# DM04mux.net
KiCad netlist of a schematic drawn in EAGLE
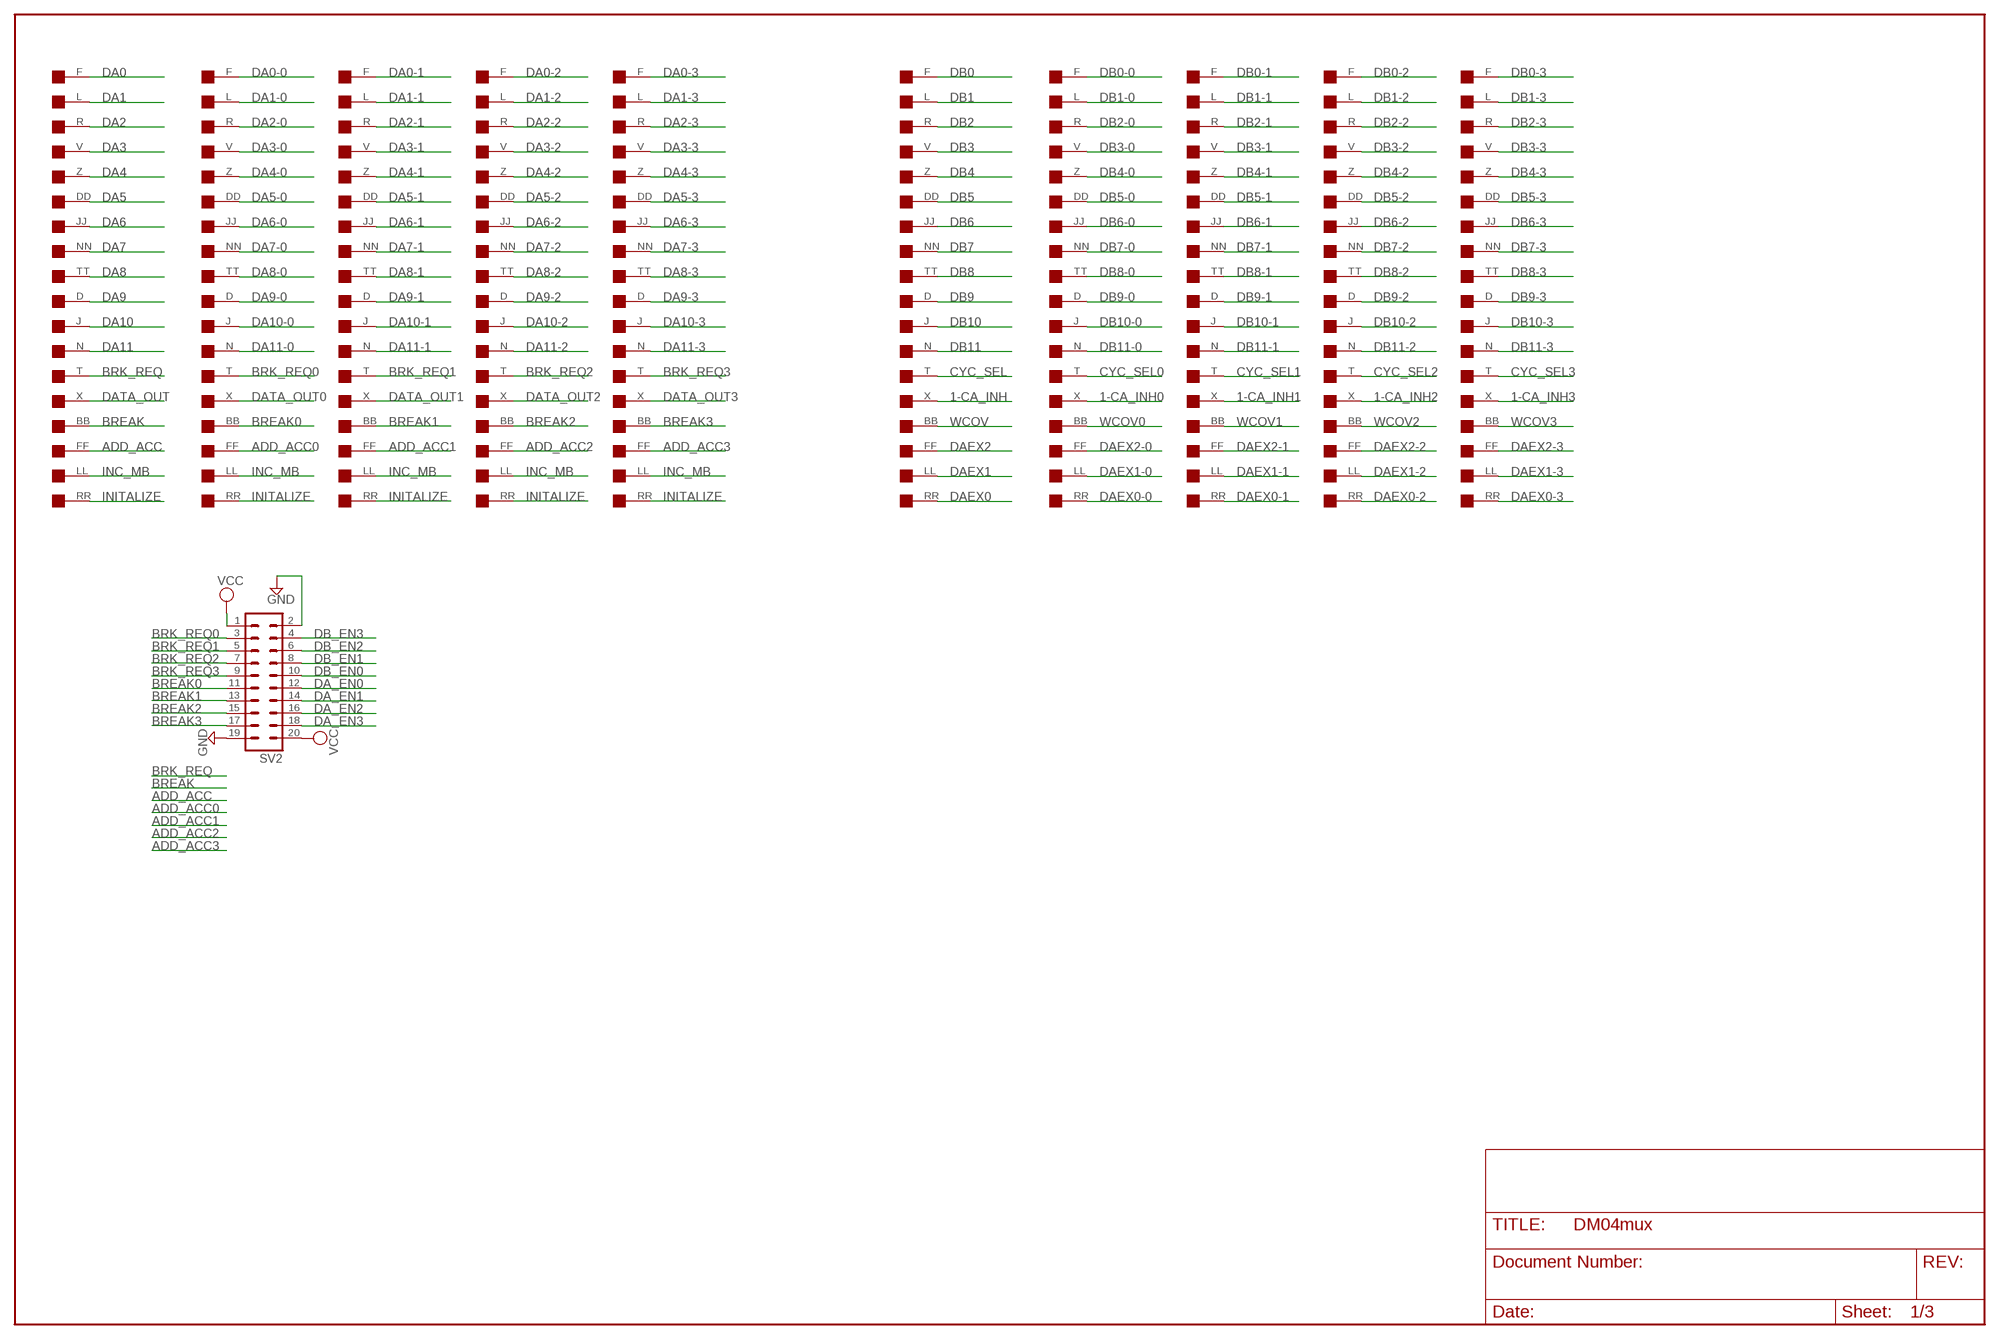
[diagram p0: schematic, sheet 1]
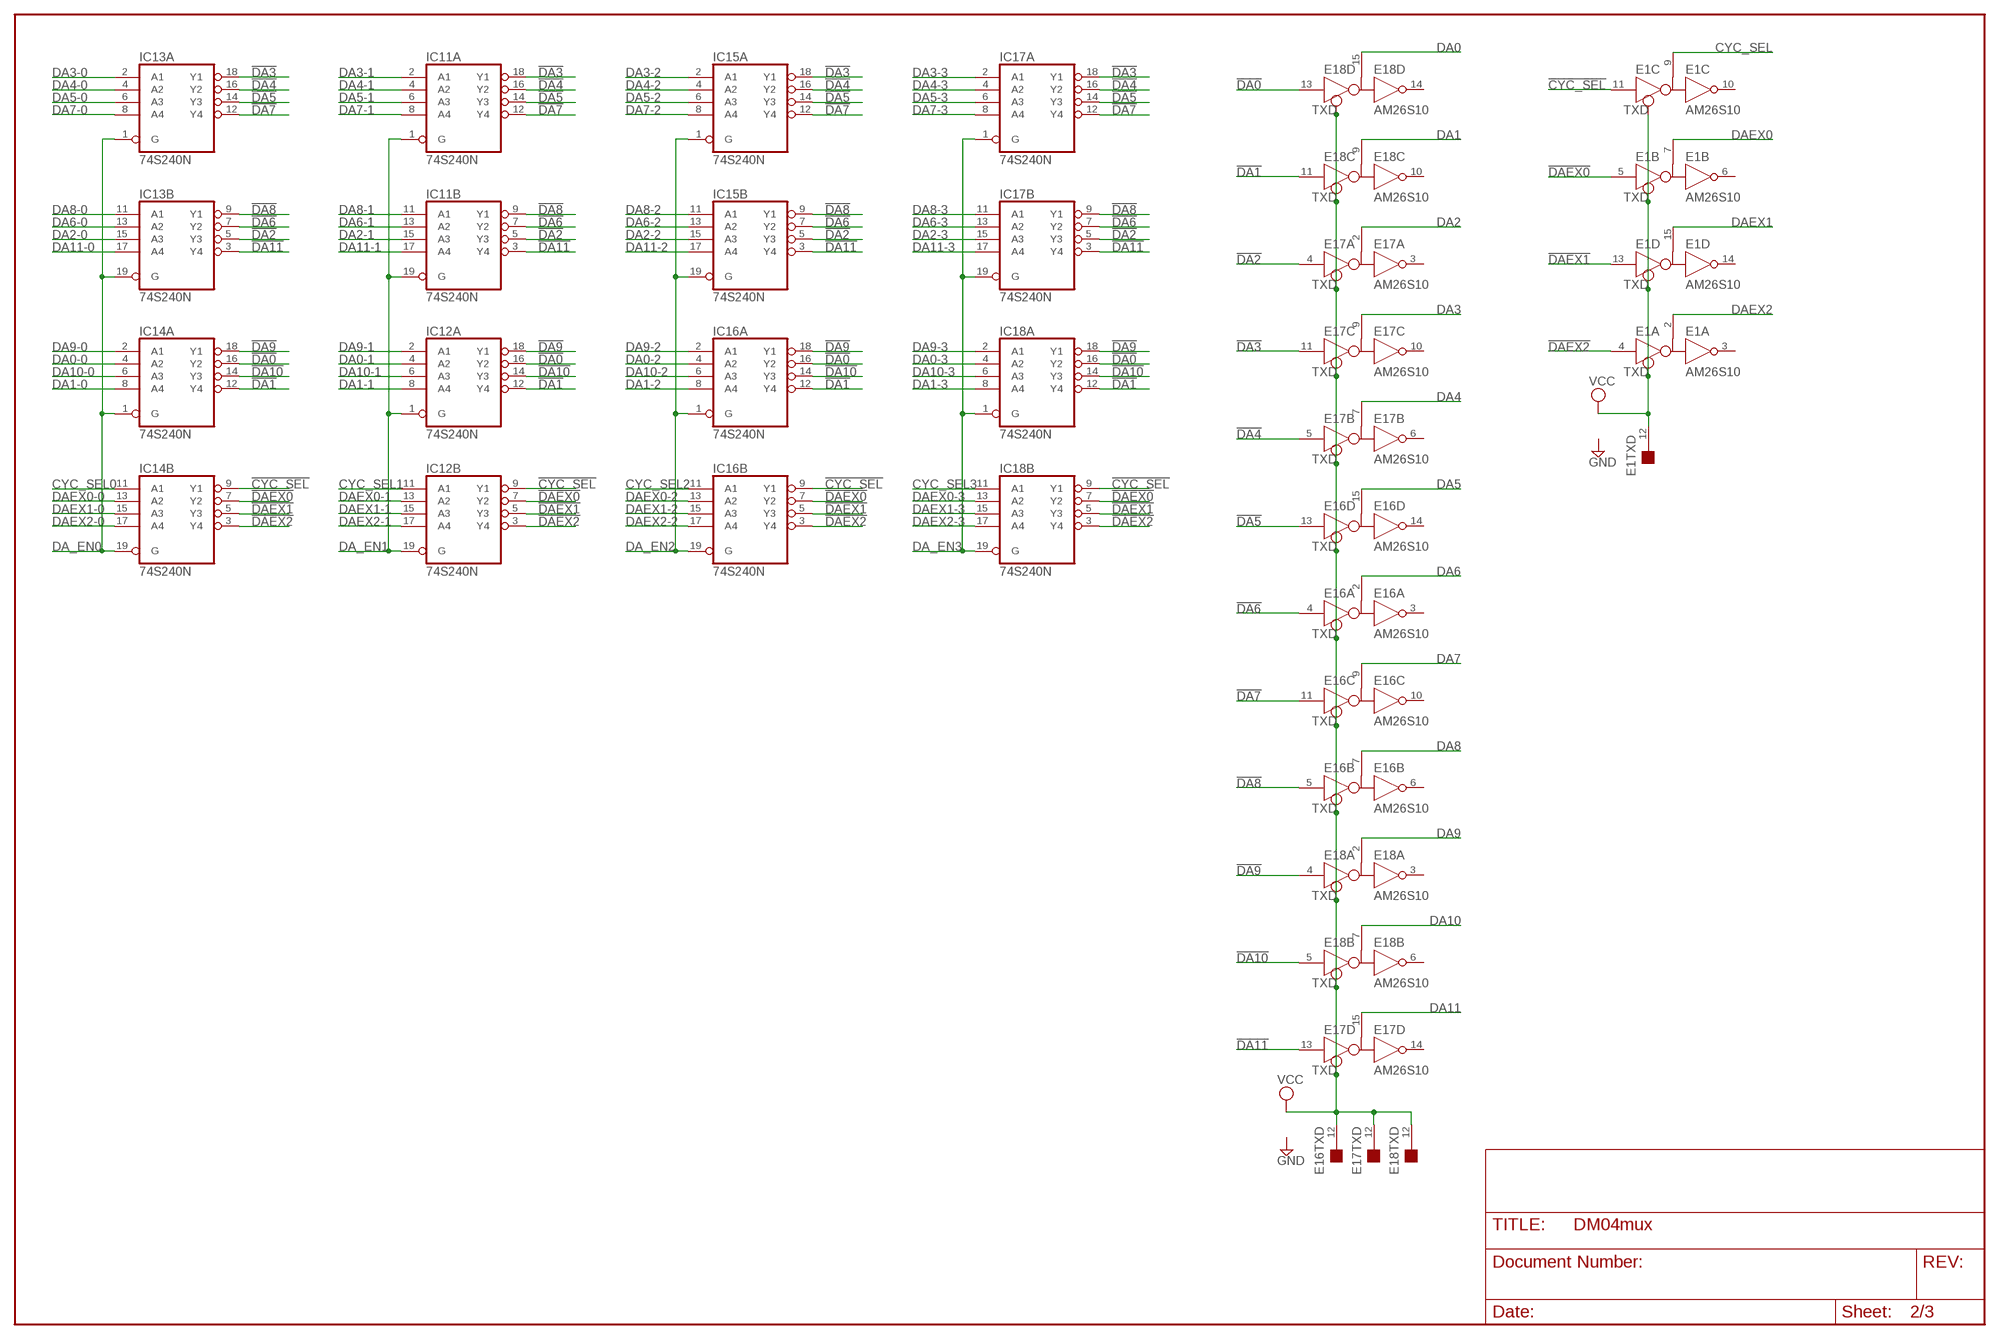
[diagram p1: schematic, sheet 2]
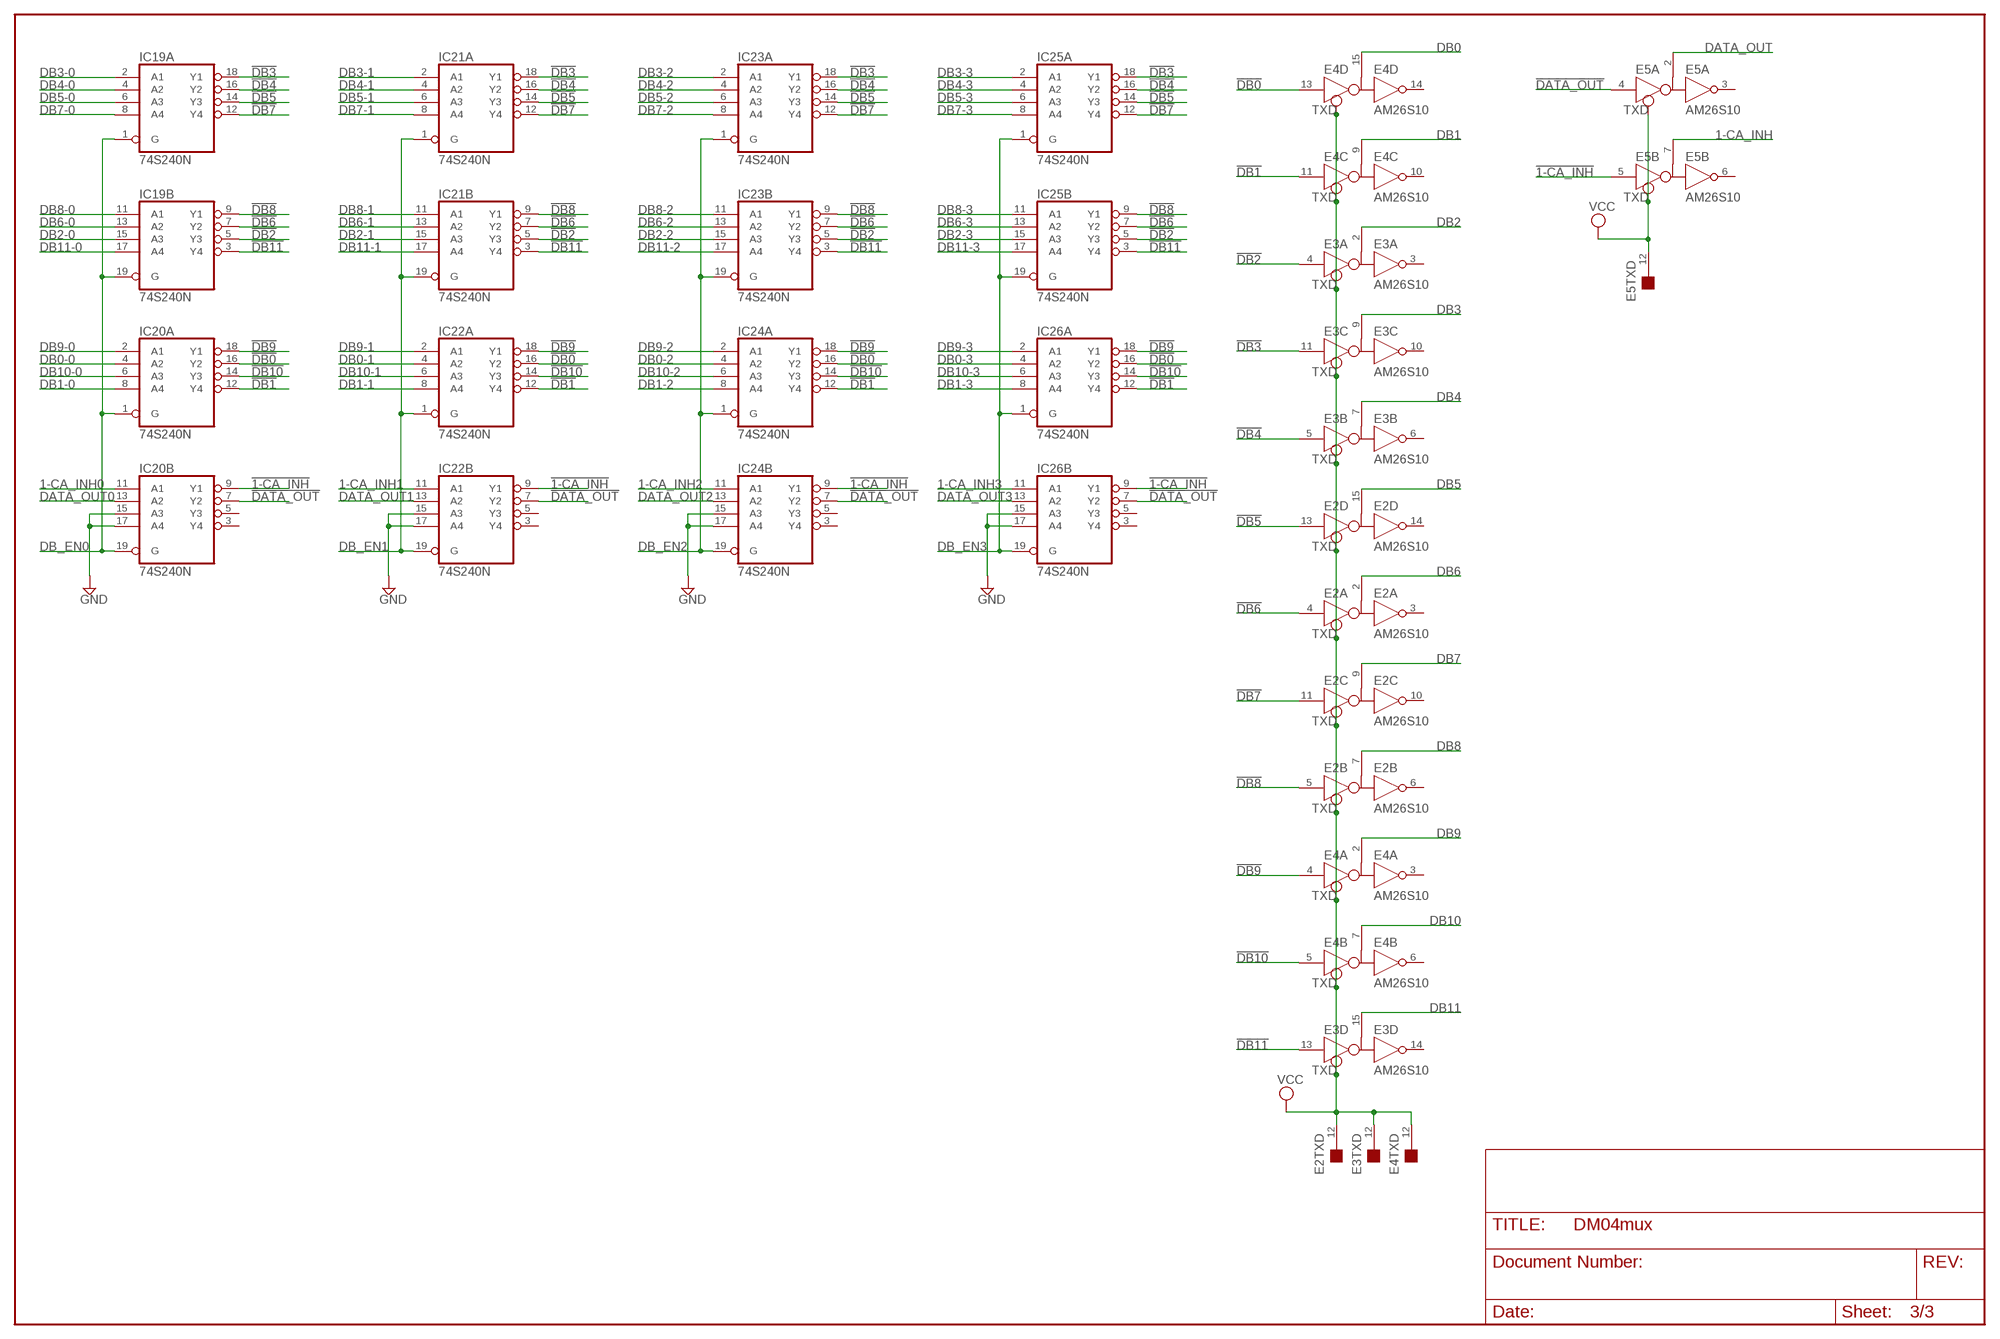
[diagram p2: schematic, sheet 3]

(export (version "E")
  (design (tool "Eeschema 10.0.6"))
  (components
    (comp (ref "SV2")
      (value "MA10-2")
      (footprint "eagle-import:MA10-2")
      (libsource (lib "eagle-import") (part "MA10-2"))
    )
    (comp (ref "U$1")
      (value "BC08J")
      (footprint "eagle-import:DEC40PINV")
      (libsource (lib "eagle-import") (part "BC08J"))
    )
    (comp (ref "U$2")
      (value "BC08J")
      (footprint "eagle-import:DEC40PINV")
      (libsource (lib "eagle-import") (part "BC08J"))
    )
    (comp (ref "U$3")
      (value "BC08J")
      (footprint "eagle-import:DEC40PINV")
      (libsource (lib "eagle-import") (part "BC08J"))
    )
    (comp (ref "U$4")
      (value "BC08J")
      (footprint "eagle-import:DEC40PINV")
      (libsource (lib "eagle-import") (part "BC08J"))
    )
    (comp (ref "U$5")
      (value "BC08J")
      (footprint "eagle-import:DEC40PINV")
      (libsource (lib "eagle-import") (part "BC08J"))
    )
    (comp (ref "U$6")
      (value "BC08J")
      (footprint "eagle-import:DEC40PINV")
      (libsource (lib "eagle-import") (part "BC08J"))
    )
    (comp (ref "U$7")
      (value "BC08J")
      (footprint "eagle-import:DEC40PINV")
      (libsource (lib "eagle-import") (part "BC08J"))
    )
    (comp (ref "U$8")
      (value "BC08J")
      (footprint "eagle-import:DEC40PINV")
      (libsource (lib "eagle-import") (part "BC08J"))
    )
    (comp (ref "U$9")
      (value "BC08J")
      (footprint "eagle-import:DEC40PINV")
      (libsource (lib "eagle-import") (part "BC08J"))
    )
    (comp (ref "U$10")
      (value "BC08J")
      (footprint "eagle-import:DEC40PINV")
      (libsource (lib "eagle-import") (part "BC08J"))
    )
    (comp (ref "E1")
      (value "AM26S10")
      (footprint "eagle-import:DIL16")
      (libsource (lib "eagle-import") (part "AM26S10"))
    )
    (comp (ref "E16")
      (value "AM26S10")
      (footprint "eagle-import:DIL16")
      (libsource (lib "eagle-import") (part "AM26S10"))
    )
    (comp (ref "E17")
      (value "AM26S10")
      (footprint "eagle-import:DIL16")
      (libsource (lib "eagle-import") (part "AM26S10"))
    )
    (comp (ref "E18")
      (value "AM26S10")
      (footprint "eagle-import:DIL16")
      (libsource (lib "eagle-import") (part "AM26S10"))
    )
    (comp (ref "IC11")
      (value "74S240N")
      (footprint "eagle-import:DIL20")
      (libsource (lib "eagle-import") (part "74240NS"))
    )
    (comp (ref "IC12")
      (value "74S240N")
      (footprint "eagle-import:DIL20")
      (libsource (lib "eagle-import") (part "74240NS"))
    )
    (comp (ref "IC13")
      (value "74S240N")
      (footprint "eagle-import:DIL20")
      (libsource (lib "eagle-import") (part "74240NS"))
    )
    (comp (ref "IC14")
      (value "74S240N")
      (footprint "eagle-import:DIL20")
      (libsource (lib "eagle-import") (part "74240NS"))
    )
    (comp (ref "IC15")
      (value "74S240N")
      (footprint "eagle-import:DIL20")
      (libsource (lib "eagle-import") (part "74240NS"))
    )
    (comp (ref "IC16")
      (value "74S240N")
      (footprint "eagle-import:DIL20")
      (libsource (lib "eagle-import") (part "74240NS"))
    )
    (comp (ref "IC17")
      (value "74S240N")
      (footprint "eagle-import:DIL20")
      (libsource (lib "eagle-import") (part "74240NS"))
    )
    (comp (ref "IC18")
      (value "74S240N")
      (footprint "eagle-import:DIL20")
      (libsource (lib "eagle-import") (part "74240NS"))
    )
    (comp (ref "E2")
      (value "AM26S10")
      (footprint "eagle-import:DIL16")
      (libsource (lib "eagle-import") (part "AM26S10"))
    )
    (comp (ref "E3")
      (value "AM26S10")
      (footprint "eagle-import:DIL16")
      (libsource (lib "eagle-import") (part "AM26S10"))
    )
    (comp (ref "E4")
      (value "AM26S10")
      (footprint "eagle-import:DIL16")
      (libsource (lib "eagle-import") (part "AM26S10"))
    )
    (comp (ref "E5")
      (value "AM26S10")
      (footprint "eagle-import:DIL16")
      (libsource (lib "eagle-import") (part "AM26S10"))
    )
    (comp (ref "IC19")
      (value "74S240N")
      (footprint "eagle-import:DIL20")
      (libsource (lib "eagle-import") (part "74240NS"))
    )
    (comp (ref "IC20")
      (value "74S240N")
      (footprint "eagle-import:DIL20")
      (libsource (lib "eagle-import") (part "74240NS"))
    )
    (comp (ref "IC21")
      (value "74S240N")
      (footprint "eagle-import:DIL20")
      (libsource (lib "eagle-import") (part "74240NS"))
    )
    (comp (ref "IC22")
      (value "74S240N")
      (footprint "eagle-import:DIL20")
      (libsource (lib "eagle-import") (part "74240NS"))
    )
    (comp (ref "IC23")
      (value "74S240N")
      (footprint "eagle-import:DIL20")
      (libsource (lib "eagle-import") (part "74240NS"))
    )
    (comp (ref "IC24")
      (value "74S240N")
      (footprint "eagle-import:DIL20")
      (libsource (lib "eagle-import") (part "74240NS"))
    )
    (comp (ref "IC25")
      (value "74S240N")
      (footprint "eagle-import:DIL20")
      (libsource (lib "eagle-import") (part "74240NS"))
    )
    (comp (ref "IC26")
      (value "74S240N")
      (footprint "eagle-import:DIL20")
      (libsource (lib "eagle-import") (part "74240NS"))
    )
  )
  (nets
    (net (code "1") (name "1-CA_INH") (class "Default")
      (node (ref "E5") (pin "7") (pinfunction "B_7") (pintype "bidirectional"))
      (node (ref "U$6") (pin "X") (pinfunction "1_X") (pintype "bidirectional"))
    )
    (net (code "2") (name "1-CA_INH0") (class "Default")
      (node (ref "IC20") (pin "11") (pinfunction "A1_11") (pintype "input"))
      (node (ref "U$7") (pin "X") (pinfunction "1_X") (pintype "bidirectional"))
    )
    (net (code "3") (name "1-CA_INH1") (class "Default")
      (node (ref "IC22") (pin "11") (pinfunction "A1_11") (pintype "input"))
      (node (ref "U$8") (pin "X") (pinfunction "1_X") (pintype "bidirectional"))
    )
    (net (code "4") (name "1-CA_INH2") (class "Default")
      (node (ref "IC24") (pin "11") (pinfunction "A1_11") (pintype "input"))
      (node (ref "U$9") (pin "X") (pinfunction "1_X") (pintype "bidirectional"))
    )
    (net (code "5") (name "1-CA_INH3") (class "Default")
      (node (ref "IC26") (pin "11") (pinfunction "A1_11") (pintype "input"))
      (node (ref "U$10") (pin "X") (pinfunction "1_X") (pintype "bidirectional"))
    )
    (net (code "6") (name "ADD_ACC") (class "Default")
      (node (ref "U$1") (pin "FF") (pinfunction "1_FF") (pintype "bidirectional"))
    )
    (net (code "7") (name "ADD_ACC0") (class "Default")
      (node (ref "U$2") (pin "FF") (pinfunction "1_FF") (pintype "bidirectional"))
    )
    (net (code "8") (name "ADD_ACC1") (class "Default")
      (node (ref "U$3") (pin "FF") (pinfunction "1_FF") (pintype "bidirectional"))
    )
    (net (code "9") (name "ADD_ACC2") (class "Default")
      (node (ref "U$4") (pin "FF") (pinfunction "1_FF") (pintype "bidirectional"))
    )
    (net (code "10") (name "ADD_ACC3") (class "Default")
      (node (ref "U$5") (pin "FF") (pinfunction "1_FF") (pintype "bidirectional"))
    )
    (net (code "11") (name "BREAK") (class "Default")
      (node (ref "U$1") (pin "BB") (pinfunction "1_BB") (pintype "bidirectional"))
    )
    (net (code "12") (name "BREAK0") (class "Default")
      (node (ref "SV2") (pin "11") (pinfunction "11_11") (pintype "passive"))
      (node (ref "U$2") (pin "BB") (pinfunction "1_BB") (pintype "bidirectional"))
    )
    (net (code "13") (name "BREAK1") (class "Default")
      (node (ref "SV2") (pin "13") (pinfunction "13_13") (pintype "passive"))
      (node (ref "U$3") (pin "BB") (pinfunction "1_BB") (pintype "bidirectional"))
    )
    (net (code "14") (name "BREAK2") (class "Default")
      (node (ref "SV2") (pin "15") (pinfunction "15_15") (pintype "passive"))
      (node (ref "U$4") (pin "BB") (pinfunction "1_BB") (pintype "bidirectional"))
    )
    (net (code "15") (name "BREAK3") (class "Default")
      (node (ref "SV2") (pin "17") (pinfunction "17_17") (pintype "passive"))
      (node (ref "U$5") (pin "BB") (pinfunction "1_BB") (pintype "bidirectional"))
    )
    (net (code "16") (name "BRK_REQ") (class "Default")
      (node (ref "U$1") (pin "T") (pinfunction "1_T") (pintype "bidirectional"))
    )
    (net (code "17") (name "BRK_REQ0") (class "Default")
      (node (ref "SV2") (pin "3") (pinfunction "3_3") (pintype "passive"))
      (node (ref "U$2") (pin "T") (pinfunction "1_T") (pintype "bidirectional"))
    )
    (net (code "18") (name "BRK_REQ1") (class "Default")
      (node (ref "SV2") (pin "5") (pinfunction "5_5") (pintype "passive"))
      (node (ref "U$3") (pin "T") (pinfunction "1_T") (pintype "bidirectional"))
    )
    (net (code "19") (name "BRK_REQ2") (class "Default")
      (node (ref "SV2") (pin "7") (pinfunction "7_7") (pintype "passive"))
      (node (ref "U$4") (pin "T") (pinfunction "1_T") (pintype "bidirectional"))
    )
    (net (code "20") (name "BRK_REQ3") (class "Default")
      (node (ref "SV2") (pin "9") (pinfunction "9_9") (pintype "passive"))
      (node (ref "U$5") (pin "T") (pinfunction "1_T") (pintype "bidirectional"))
    )
    (net (code "21") (name "CYC_SEL") (class "Default")
      (node (ref "E1") (pin "9") (pinfunction "B_9") (pintype "bidirectional"))
      (node (ref "U$6") (pin "T") (pinfunction "1_T") (pintype "bidirectional"))
    )
    (net (code "22") (name "CYC_SEL0") (class "Default")
      (node (ref "IC14") (pin "11") (pinfunction "A1_11") (pintype "input"))
      (node (ref "U$7") (pin "T") (pinfunction "1_T") (pintype "bidirectional"))
    )
    (net (code "23") (name "CYC_SEL1") (class "Default")
      (node (ref "IC12") (pin "11") (pinfunction "A1_11") (pintype "input"))
      (node (ref "U$8") (pin "T") (pinfunction "1_T") (pintype "bidirectional"))
    )
    (net (code "24") (name "CYC_SEL2") (class "Default")
      (node (ref "IC16") (pin "11") (pinfunction "A1_11") (pintype "input"))
      (node (ref "U$9") (pin "T") (pinfunction "1_T") (pintype "bidirectional"))
    )
    (net (code "25") (name "CYC_SEL3") (class "Default")
      (node (ref "IC18") (pin "11") (pinfunction "A1_11") (pintype "input"))
      (node (ref "U$10") (pin "T") (pinfunction "1_T") (pintype "bidirectional"))
    )
    (net (code "26") (name "DA0") (class "Default")
      (node (ref "E18") (pin "15") (pinfunction "B_15") (pintype "bidirectional"))
      (node (ref "U$1") (pin "F") (pinfunction "1_F") (pintype "bidirectional"))
    )
    (net (code "27") (name "DA0-0") (class "Default")
      (node (ref "IC14") (pin "4") (pinfunction "A2_4") (pintype "input"))
      (node (ref "U$2") (pin "F") (pinfunction "1_F") (pintype "bidirectional"))
    )
    (net (code "28") (name "DA0-1") (class "Default")
      (node (ref "IC12") (pin "4") (pinfunction "A2_4") (pintype "input"))
      (node (ref "U$3") (pin "F") (pinfunction "1_F") (pintype "bidirectional"))
    )
    (net (code "29") (name "DA0-2") (class "Default")
      (node (ref "IC16") (pin "4") (pinfunction "A2_4") (pintype "input"))
      (node (ref "U$4") (pin "F") (pinfunction "1_F") (pintype "bidirectional"))
    )
    (net (code "30") (name "DA0-3") (class "Default")
      (node (ref "IC18") (pin "4") (pinfunction "A2_4") (pintype "input"))
      (node (ref "U$5") (pin "F") (pinfunction "1_F") (pintype "bidirectional"))
    )
    (net (code "31") (name "DA1") (class "Default")
      (node (ref "E18") (pin "9") (pinfunction "B_9") (pintype "bidirectional"))
      (node (ref "U$1") (pin "L") (pinfunction "1_L") (pintype "bidirectional"))
    )
    (net (code "32") (name "DA1-0") (class "Default")
      (node (ref "IC14") (pin "8") (pinfunction "A4_8") (pintype "input"))
      (node (ref "U$2") (pin "L") (pinfunction "1_L") (pintype "bidirectional"))
    )
    (net (code "33") (name "DA1-1") (class "Default")
      (node (ref "IC12") (pin "8") (pinfunction "A4_8") (pintype "input"))
      (node (ref "U$3") (pin "L") (pinfunction "1_L") (pintype "bidirectional"))
    )
    (net (code "34") (name "DA1-2") (class "Default")
      (node (ref "IC16") (pin "8") (pinfunction "A4_8") (pintype "input"))
      (node (ref "U$4") (pin "L") (pinfunction "1_L") (pintype "bidirectional"))
    )
    (net (code "35") (name "DA1-3") (class "Default")
      (node (ref "IC18") (pin "8") (pinfunction "A4_8") (pintype "input"))
      (node (ref "U$5") (pin "L") (pinfunction "1_L") (pintype "bidirectional"))
    )
    (net (code "36") (name "DA2") (class "Default")
      (node (ref "E17") (pin "2") (pinfunction "B_2") (pintype "bidirectional"))
      (node (ref "U$1") (pin "R") (pinfunction "1_R") (pintype "bidirectional"))
    )
    (net (code "37") (name "DA2-0") (class "Default")
      (node (ref "IC13") (pin "15") (pinfunction "A3_15") (pintype "input"))
      (node (ref "U$2") (pin "R") (pinfunction "1_R") (pintype "bidirectional"))
    )
    (net (code "38") (name "DA2-1") (class "Default")
      (node (ref "IC11") (pin "15") (pinfunction "A3_15") (pintype "input"))
      (node (ref "U$3") (pin "R") (pinfunction "1_R") (pintype "bidirectional"))
    )
    (net (code "39") (name "DA2-2") (class "Default")
      (node (ref "IC15") (pin "15") (pinfunction "A3_15") (pintype "input"))
      (node (ref "U$4") (pin "R") (pinfunction "1_R") (pintype "bidirectional"))
    )
    (net (code "40") (name "DA2-3") (class "Default")
      (node (ref "IC17") (pin "15") (pinfunction "A3_15") (pintype "input"))
      (node (ref "U$5") (pin "R") (pinfunction "1_R") (pintype "bidirectional"))
    )
    (net (code "41") (name "DA3") (class "Default")
      (node (ref "E17") (pin "9") (pinfunction "B_9") (pintype "bidirectional"))
      (node (ref "U$1") (pin "V") (pinfunction "1_V") (pintype "bidirectional"))
    )
    (net (code "42") (name "DA3-0") (class "Default")
      (node (ref "IC13") (pin "2") (pinfunction "A1_2") (pintype "input"))
      (node (ref "U$2") (pin "V") (pinfunction "1_V") (pintype "bidirectional"))
    )
    (net (code "43") (name "DA3-1") (class "Default")
      (node (ref "IC11") (pin "2") (pinfunction "A1_2") (pintype "input"))
      (node (ref "U$3") (pin "V") (pinfunction "1_V") (pintype "bidirectional"))
    )
    (net (code "44") (name "DA3-2") (class "Default")
      (node (ref "IC15") (pin "2") (pinfunction "A1_2") (pintype "input"))
      (node (ref "U$4") (pin "V") (pinfunction "1_V") (pintype "bidirectional"))
    )
    (net (code "45") (name "DA3-3") (class "Default")
      (node (ref "IC17") (pin "2") (pinfunction "A1_2") (pintype "input"))
      (node (ref "U$5") (pin "V") (pinfunction "1_V") (pintype "bidirectional"))
    )
    (net (code "46") (name "DA4") (class "Default")
      (node (ref "E17") (pin "7") (pinfunction "B_7") (pintype "bidirectional"))
      (node (ref "U$1") (pin "Z") (pinfunction "1_Z") (pintype "bidirectional"))
    )
    (net (code "47") (name "DA4-0") (class "Default")
      (node (ref "IC13") (pin "4") (pinfunction "A2_4") (pintype "input"))
      (node (ref "U$2") (pin "Z") (pinfunction "1_Z") (pintype "bidirectional"))
    )
    (net (code "48") (name "DA4-1") (class "Default")
      (node (ref "IC11") (pin "4") (pinfunction "A2_4") (pintype "input"))
      (node (ref "U$3") (pin "Z") (pinfunction "1_Z") (pintype "bidirectional"))
    )
    (net (code "49") (name "DA4-2") (class "Default")
      (node (ref "IC15") (pin "4") (pinfunction "A2_4") (pintype "input"))
      (node (ref "U$4") (pin "Z") (pinfunction "1_Z") (pintype "bidirectional"))
    )
    (net (code "50") (name "DA4-3") (class "Default")
      (node (ref "IC17") (pin "4") (pinfunction "A2_4") (pintype "input"))
      (node (ref "U$5") (pin "Z") (pinfunction "1_Z") (pintype "bidirectional"))
    )
    (net (code "51") (name "DA5") (class "Default")
      (node (ref "E16") (pin "15") (pinfunction "B_15") (pintype "bidirectional"))
      (node (ref "U$1") (pin "DD") (pinfunction "1_DD") (pintype "bidirectional"))
    )
    (net (code "52") (name "DA5-0") (class "Default")
      (node (ref "IC13") (pin "6") (pinfunction "A3_6") (pintype "input"))
      (node (ref "U$2") (pin "DD") (pinfunction "1_DD") (pintype "bidirectional"))
    )
    (net (code "53") (name "DA5-1") (class "Default")
      (node (ref "IC11") (pin "6") (pinfunction "A3_6") (pintype "input"))
      (node (ref "U$3") (pin "DD") (pinfunction "1_DD") (pintype "bidirectional"))
    )
    (net (code "54") (name "DA5-2") (class "Default")
      (node (ref "IC15") (pin "6") (pinfunction "A3_6") (pintype "input"))
      (node (ref "U$4") (pin "DD") (pinfunction "1_DD") (pintype "bidirectional"))
    )
    (net (code "55") (name "DA5-3") (class "Default")
      (node (ref "IC17") (pin "6") (pinfunction "A3_6") (pintype "input"))
      (node (ref "U$5") (pin "DD") (pinfunction "1_DD") (pintype "bidirectional"))
    )
    (net (code "56") (name "DA6") (class "Default")
      (node (ref "E16") (pin "2") (pinfunction "B_2") (pintype "bidirectional"))
      (node (ref "U$1") (pin "JJ") (pinfunction "1_JJ") (pintype "bidirectional"))
    )
    (net (code "57") (name "DA6-0") (class "Default")
      (node (ref "IC13") (pin "13") (pinfunction "A2_13") (pintype "input"))
      (node (ref "U$2") (pin "JJ") (pinfunction "1_JJ") (pintype "bidirectional"))
    )
    (net (code "58") (name "DA6-1") (class "Default")
      (node (ref "IC11") (pin "13") (pinfunction "A2_13") (pintype "input"))
      (node (ref "U$3") (pin "JJ") (pinfunction "1_JJ") (pintype "bidirectional"))
    )
    (net (code "59") (name "DA6-2") (class "Default")
      (node (ref "IC15") (pin "13") (pinfunction "A2_13") (pintype "input"))
      (node (ref "U$4") (pin "JJ") (pinfunction "1_JJ") (pintype "bidirectional"))
    )
    (net (code "60") (name "DA6-3") (class "Default")
      (node (ref "IC17") (pin "13") (pinfunction "A2_13") (pintype "input"))
      (node (ref "U$5") (pin "JJ") (pinfunction "1_JJ") (pintype "bidirectional"))
    )
    (net (code "61") (name "DA7") (class "Default")
      (node (ref "E16") (pin "9") (pinfunction "B_9") (pintype "bidirectional"))
      (node (ref "U$1") (pin "NN") (pinfunction "1_NN") (pintype "bidirectional"))
    )
    (net (code "62") (name "DA7-0") (class "Default")
      (node (ref "IC13") (pin "8") (pinfunction "A4_8") (pintype "input"))
      (node (ref "U$2") (pin "NN") (pinfunction "1_NN") (pintype "bidirectional"))
    )
    (net (code "63") (name "DA7-1") (class "Default")
      (node (ref "IC11") (pin "8") (pinfunction "A4_8") (pintype "input"))
      (node (ref "U$3") (pin "NN") (pinfunction "1_NN") (pintype "bidirectional"))
    )
    (net (code "64") (name "DA7-2") (class "Default")
      (node (ref "IC15") (pin "8") (pinfunction "A4_8") (pintype "input"))
      (node (ref "U$4") (pin "NN") (pinfunction "1_NN") (pintype "bidirectional"))
    )
    (net (code "65") (name "DA7-3") (class "Default")
      (node (ref "IC17") (pin "8") (pinfunction "A4_8") (pintype "input"))
      (node (ref "U$5") (pin "NN") (pinfunction "1_NN") (pintype "bidirectional"))
    )
    (net (code "66") (name "DA8") (class "Default")
      (node (ref "E16") (pin "7") (pinfunction "B_7") (pintype "bidirectional"))
      (node (ref "U$1") (pin "TT") (pinfunction "1_TT") (pintype "bidirectional"))
    )
    (net (code "67") (name "DA8-0") (class "Default")
      (node (ref "IC13") (pin "11") (pinfunction "A1_11") (pintype "input"))
      (node (ref "U$2") (pin "TT") (pinfunction "1_TT") (pintype "bidirectional"))
    )
    (net (code "68") (name "DA8-1") (class "Default")
      (node (ref "IC11") (pin "11") (pinfunction "A1_11") (pintype "input"))
      (node (ref "U$3") (pin "TT") (pinfunction "1_TT") (pintype "bidirectional"))
    )
    (net (code "69") (name "DA8-2") (class "Default")
      (node (ref "IC15") (pin "11") (pinfunction "A1_11") (pintype "input"))
      (node (ref "U$4") (pin "TT") (pinfunction "1_TT") (pintype "bidirectional"))
    )
    (net (code "70") (name "DA8-3") (class "Default")
      (node (ref "IC17") (pin "11") (pinfunction "A1_11") (pintype "input"))
      (node (ref "U$5") (pin "TT") (pinfunction "1_TT") (pintype "bidirectional"))
    )
    (net (code "71") (name "DA9") (class "Default")
      (node (ref "E18") (pin "2") (pinfunction "B_2") (pintype "bidirectional"))
      (node (ref "U$1") (pin "D") (pinfunction "1_D") (pintype "bidirectional"))
    )
    (net (code "72") (name "DA9-0") (class "Default")
      (node (ref "IC14") (pin "2") (pinfunction "A1_2") (pintype "input"))
      (node (ref "U$2") (pin "D") (pinfunction "1_D") (pintype "bidirectional"))
    )
    (net (code "73") (name "DA9-1") (class "Default")
      (node (ref "IC12") (pin "2") (pinfunction "A1_2") (pintype "input"))
      (node (ref "U$3") (pin "D") (pinfunction "1_D") (pintype "bidirectional"))
    )
    (net (code "74") (name "DA9-2") (class "Default")
      (node (ref "IC16") (pin "2") (pinfunction "A1_2") (pintype "input"))
      (node (ref "U$4") (pin "D") (pinfunction "1_D") (pintype "bidirectional"))
    )
    (net (code "75") (name "DA9-3") (class "Default")
      (node (ref "IC18") (pin "2") (pinfunction "A1_2") (pintype "input"))
      (node (ref "U$5") (pin "D") (pinfunction "1_D") (pintype "bidirectional"))
    )
    (net (code "76") (name "DA10") (class "Default")
      (node (ref "E18") (pin "7") (pinfunction "B_7") (pintype "bidirectional"))
      (node (ref "U$1") (pin "J") (pinfunction "1_J") (pintype "bidirectional"))
    )
    (net (code "77") (name "DA10-0") (class "Default")
      (node (ref "IC14") (pin "6") (pinfunction "A3_6") (pintype "input"))
      (node (ref "U$2") (pin "J") (pinfunction "1_J") (pintype "bidirectional"))
    )
    (net (code "78") (name "DA10-1") (class "Default")
      (node (ref "IC12") (pin "6") (pinfunction "A3_6") (pintype "input"))
      (node (ref "U$3") (pin "J") (pinfunction "1_J") (pintype "bidirectional"))
    )
    (net (code "79") (name "DA10-2") (class "Default")
      (node (ref "IC16") (pin "6") (pinfunction "A3_6") (pintype "input"))
      (node (ref "U$4") (pin "J") (pinfunction "1_J") (pintype "bidirectional"))
    )
    (net (code "80") (name "DA10-3") (class "Default")
      (node (ref "IC18") (pin "6") (pinfunction "A3_6") (pintype "input"))
      (node (ref "U$5") (pin "J") (pinfunction "1_J") (pintype "bidirectional"))
    )
    (net (code "81") (name "DA11") (class "Default")
      (node (ref "E17") (pin "15") (pinfunction "B_15") (pintype "bidirectional"))
      (node (ref "U$1") (pin "N") (pinfunction "1_N") (pintype "bidirectional"))
    )
    (net (code "82") (name "DA11-0") (class "Default")
      (node (ref "IC13") (pin "17") (pinfunction "A4_17") (pintype "input"))
      (node (ref "U$2") (pin "N") (pinfunction "1_N") (pintype "bidirectional"))
    )
    (net (code "83") (name "DA11-1") (class "Default")
      (node (ref "IC11") (pin "17") (pinfunction "A4_17") (pintype "input"))
      (node (ref "U$3") (pin "N") (pinfunction "1_N") (pintype "bidirectional"))
    )
    (net (code "84") (name "DA11-2") (class "Default")
      (node (ref "IC15") (pin "17") (pinfunction "A4_17") (pintype "input"))
      (node (ref "U$4") (pin "N") (pinfunction "1_N") (pintype "bidirectional"))
    )
    (net (code "85") (name "DA11-3") (class "Default")
      (node (ref "IC17") (pin "17") (pinfunction "A4_17") (pintype "input"))
      (node (ref "U$5") (pin "N") (pinfunction "1_N") (pintype "bidirectional"))
    )
    (net (code "86") (name "DAEX0") (class "Default")
      (node (ref "E1") (pin "7") (pinfunction "B_7") (pintype "bidirectional"))
      (node (ref "U$6") (pin "RR") (pinfunction "1_RR") (pintype "bidirectional"))
    )
    (net (code "87") (name "DAEX0-0") (class "Default")
      (node (ref "IC14") (pin "13") (pinfunction "A2_13") (pintype "input"))
      (node (ref "U$7") (pin "RR") (pinfunction "1_RR") (pintype "bidirectional"))
    )
    (net (code "88") (name "DAEX0-1") (class "Default")
      (node (ref "IC12") (pin "13") (pinfunction "A2_13") (pintype "input"))
      (node (ref "U$8") (pin "RR") (pinfunction "1_RR") (pintype "bidirectional"))
    )
    (net (code "89") (name "DAEX0-2") (class "Default")
      (node (ref "IC16") (pin "13") (pinfunction "A2_13") (pintype "input"))
      (node (ref "U$9") (pin "RR") (pinfunction "1_RR") (pintype "bidirectional"))
    )
    (net (code "90") (name "DAEX0-3") (class "Default")
      (node (ref "IC18") (pin "13") (pinfunction "A2_13") (pintype "input"))
      (node (ref "U$10") (pin "RR") (pinfunction "1_RR") (pintype "bidirectional"))
    )
    (net (code "91") (name "DAEX1") (class "Default")
      (node (ref "E1") (pin "15") (pinfunction "B_15") (pintype "bidirectional"))
      (node (ref "U$6") (pin "LL") (pinfunction "1_LL") (pintype "bidirectional"))
    )
    (net (code "92") (name "DAEX1-0") (class "Default")
      (node (ref "IC14") (pin "15") (pinfunction "A3_15") (pintype "input"))
      (node (ref "U$7") (pin "LL") (pinfunction "1_LL") (pintype "bidirectional"))
    )
    (net (code "93") (name "DAEX1-1") (class "Default")
      (node (ref "IC12") (pin "15") (pinfunction "A3_15") (pintype "input"))
      (node (ref "U$8") (pin "LL") (pinfunction "1_LL") (pintype "bidirectional"))
    )
    (net (code "94") (name "DAEX1-2") (class "Default")
      (node (ref "IC16") (pin "15") (pinfunction "A3_15") (pintype "input"))
      (node (ref "U$9") (pin "LL") (pinfunction "1_LL") (pintype "bidirectional"))
    )
    (net (code "95") (name "DAEX1-3") (class "Default")
      (node (ref "IC18") (pin "15") (pinfunction "A3_15") (pintype "input"))
      (node (ref "U$10") (pin "LL") (pinfunction "1_LL") (pintype "bidirectional"))
    )
    (net (code "96") (name "DAEX2") (class "Default")
      (node (ref "E1") (pin "2") (pinfunction "B_2") (pintype "bidirectional"))
      (node (ref "U$6") (pin "FF") (pinfunction "1_FF") (pintype "bidirectional"))
    )
    (net (code "97") (name "DAEX2-0") (class "Default")
      (node (ref "IC14") (pin "17") (pinfunction "A4_17") (pintype "input"))
      (node (ref "U$7") (pin "FF") (pinfunction "1_FF") (pintype "bidirectional"))
    )
    (net (code "98") (name "DAEX2-1") (class "Default")
      (node (ref "IC12") (pin "17") (pinfunction "A4_17") (pintype "input"))
      (node (ref "U$8") (pin "FF") (pinfunction "1_FF") (pintype "bidirectional"))
    )
    (net (code "99") (name "DAEX2-2") (class "Default")
      (node (ref "IC16") (pin "17") (pinfunction "A4_17") (pintype "input"))
      (node (ref "U$9") (pin "FF") (pinfunction "1_FF") (pintype "bidirectional"))
    )
    (net (code "100") (name "DAEX2-3") (class "Default")
      (node (ref "IC18") (pin "17") (pinfunction "A4_17") (pintype "input"))
      (node (ref "U$10") (pin "FF") (pinfunction "1_FF") (pintype "bidirectional"))
    )
    (net (code "101") (name "DATA_OUT") (class "Default")
      (node (ref "E5") (pin "2") (pinfunction "B_2") (pintype "bidirectional"))
      (node (ref "U$1") (pin "X") (pinfunction "1_X") (pintype "bidirectional"))
    )
    (net (code "102") (name "DATA_OUT0") (class "Default")
      (node (ref "IC20") (pin "13") (pinfunction "A2_13") (pintype "input"))
      (node (ref "U$2") (pin "X") (pinfunction "1_X") (pintype "bidirectional"))
    )
    (net (code "103") (name "DATA_OUT1") (class "Default")
      (node (ref "IC22") (pin "13") (pinfunction "A2_13") (pintype "input"))
      (node (ref "U$3") (pin "X") (pinfunction "1_X") (pintype "bidirectional"))
    )
    (net (code "104") (name "DATA_OUT2") (class "Default")
      (node (ref "IC24") (pin "13") (pinfunction "A2_13") (pintype "input"))
      (node (ref "U$4") (pin "X") (pinfunction "1_X") (pintype "bidirectional"))
    )
    (net (code "105") (name "DATA_OUT3") (class "Default")
      (node (ref "IC26") (pin "13") (pinfunction "A2_13") (pintype "input"))
      (node (ref "U$5") (pin "X") (pinfunction "1_X") (pintype "bidirectional"))
    )
    (net (code "106") (name "DA_EN0") (class "Default")
      (node (ref "IC13") (pin "1") (pinfunction "G_1") (pintype "input"))
      (node (ref "IC13") (pin "19") (pinfunction "G_19") (pintype "input"))
      (node (ref "IC14") (pin "1") (pinfunction "G_1") (pintype "input"))
      (node (ref "IC14") (pin "19") (pinfunction "G_19") (pintype "input"))
      (node (ref "SV2") (pin "12") (pinfunction "12_12") (pintype "passive"))
    )
    (net (code "107") (name "DA_EN1") (class "Default")
      (node (ref "IC11") (pin "1") (pinfunction "G_1") (pintype "input"))
      (node (ref "IC11") (pin "19") (pinfunction "G_19") (pintype "input"))
      (node (ref "IC12") (pin "1") (pinfunction "G_1") (pintype "input"))
      (node (ref "IC12") (pin "19") (pinfunction "G_19") (pintype "input"))
      (node (ref "SV2") (pin "14") (pinfunction "14_14") (pintype "passive"))
    )
    (net (code "108") (name "DA_EN2") (class "Default")
      (node (ref "IC15") (pin "1") (pinfunction "G_1") (pintype "input"))
      (node (ref "IC15") (pin "19") (pinfunction "G_19") (pintype "input"))
      (node (ref "IC16") (pin "1") (pinfunction "G_1") (pintype "input"))
      (node (ref "IC16") (pin "19") (pinfunction "G_19") (pintype "input"))
      (node (ref "SV2") (pin "16") (pinfunction "16_16") (pintype "passive"))
    )
    (net (code "109") (name "DA_EN3") (class "Default")
      (node (ref "IC17") (pin "1") (pinfunction "G_1") (pintype "input"))
      (node (ref "IC17") (pin "19") (pinfunction "G_19") (pintype "input"))
      (node (ref "IC18") (pin "1") (pinfunction "G_1") (pintype "input"))
      (node (ref "IC18") (pin "19") (pinfunction "G_19") (pintype "input"))
      (node (ref "SV2") (pin "18") (pinfunction "18_18") (pintype "passive"))
    )
    (net (code "110") (name "DB0") (class "Default")
      (node (ref "E4") (pin "15") (pinfunction "B_15") (pintype "bidirectional"))
      (node (ref "U$6") (pin "F") (pinfunction "1_F") (pintype "bidirectional"))
    )
    (net (code "111") (name "DB0-0") (class "Default")
      (node (ref "IC20") (pin "4") (pinfunction "A2_4") (pintype "input"))
      (node (ref "U$7") (pin "F") (pinfunction "1_F") (pintype "bidirectional"))
    )
    (net (code "112") (name "DB0-1") (class "Default")
      (node (ref "IC22") (pin "4") (pinfunction "A2_4") (pintype "input"))
      (node (ref "U$8") (pin "F") (pinfunction "1_F") (pintype "bidirectional"))
    )
    (net (code "113") (name "DB0-2") (class "Default")
      (node (ref "IC24") (pin "4") (pinfunction "A2_4") (pintype "input"))
      (node (ref "U$9") (pin "F") (pinfunction "1_F") (pintype "bidirectional"))
    )
    (net (code "114") (name "DB0-3") (class "Default")
      (node (ref "IC26") (pin "4") (pinfunction "A2_4") (pintype "input"))
      (node (ref "U$10") (pin "F") (pinfunction "1_F") (pintype "bidirectional"))
    )
    (net (code "115") (name "DB1") (class "Default")
      (node (ref "E4") (pin "9") (pinfunction "B_9") (pintype "bidirectional"))
      (node (ref "U$6") (pin "L") (pinfunction "1_L") (pintype "bidirectional"))
    )
    (net (code "116") (name "DB1-0") (class "Default")
      (node (ref "IC20") (pin "8") (pinfunction "A4_8") (pintype "input"))
      (node (ref "U$7") (pin "L") (pinfunction "1_L") (pintype "bidirectional"))
    )
    (net (code "117") (name "DB1-1") (class "Default")
      (node (ref "IC22") (pin "8") (pinfunction "A4_8") (pintype "input"))
      (node (ref "U$8") (pin "L") (pinfunction "1_L") (pintype "bidirectional"))
    )
    (net (code "118") (name "DB1-2") (class "Default")
      (node (ref "IC24") (pin "8") (pinfunction "A4_8") (pintype "input"))
      (node (ref "U$9") (pin "L") (pinfunction "1_L") (pintype "bidirectional"))
    )
    (net (code "119") (name "DB1-3") (class "Default")
      (node (ref "IC26") (pin "8") (pinfunction "A4_8") (pintype "input"))
      (node (ref "U$10") (pin "L") (pinfunction "1_L") (pintype "bidirectional"))
    )
    (net (code "120") (name "DB2") (class "Default")
      (node (ref "E3") (pin "2") (pinfunction "B_2") (pintype "bidirectional"))
      (node (ref "U$6") (pin "R") (pinfunction "1_R") (pintype "bidirectional"))
    )
    (net (code "121") (name "DB2-0") (class "Default")
      (node (ref "IC19") (pin "15") (pinfunction "A3_15") (pintype "input"))
      (node (ref "U$7") (pin "R") (pinfunction "1_R") (pintype "bidirectional"))
    )
    (net (code "122") (name "DB2-1") (class "Default")
      (node (ref "IC21") (pin "15") (pinfunction "A3_15") (pintype "input"))
      (node (ref "U$8") (pin "R") (pinfunction "1_R") (pintype "bidirectional"))
    )
    (net (code "123") (name "DB2-2") (class "Default")
      (node (ref "IC23") (pin "15") (pinfunction "A3_15") (pintype "input"))
      (node (ref "U$9") (pin "R") (pinfunction "1_R") (pintype "bidirectional"))
    )
    (net (code "124") (name "DB2-3") (class "Default")
      (node (ref "IC25") (pin "15") (pinfunction "A3_15") (pintype "input"))
      (node (ref "U$10") (pin "R") (pinfunction "1_R") (pintype "bidirectional"))
    )
    (net (code "125") (name "DB3") (class "Default")
      (node (ref "E3") (pin "9") (pinfunction "B_9") (pintype "bidirectional"))
      (node (ref "U$6") (pin "V") (pinfunction "1_V") (pintype "bidirectional"))
    )
    (net (code "126") (name "DB3-0") (class "Default")
      (node (ref "IC19") (pin "2") (pinfunction "A1_2") (pintype "input"))
      (node (ref "U$7") (pin "V") (pinfunction "1_V") (pintype "bidirectional"))
    )
    (net (code "127") (name "DB3-1") (class "Default")
      (node (ref "IC21") (pin "2") (pinfunction "A1_2") (pintype "input"))
      (node (ref "U$8") (pin "V") (pinfunction "1_V") (pintype "bidirectional"))
    )
    (net (code "128") (name "DB3-2") (class "Default")
      (node (ref "IC23") (pin "2") (pinfunction "A1_2") (pintype "input"))
      (node (ref "U$9") (pin "V") (pinfunction "1_V") (pintype "bidirectional"))
    )
    (net (code "129") (name "DB3-3") (class "Default")
      (node (ref "IC25") (pin "2") (pinfunction "A1_2") (pintype "input"))
      (node (ref "U$10") (pin "V") (pinfunction "1_V") (pintype "bidirectional"))
    )
    (net (code "130") (name "DB4") (class "Default")
      (node (ref "E3") (pin "7") (pinfunction "B_7") (pintype "bidirectional"))
      (node (ref "U$6") (pin "Z") (pinfunction "1_Z") (pintype "bidirectional"))
    )
    (net (code "131") (name "DB4-0") (class "Default")
      (node (ref "IC19") (pin "4") (pinfunction "A2_4") (pintype "input"))
      (node (ref "U$7") (pin "Z") (pinfunction "1_Z") (pintype "bidirectional"))
    )
    (net (code "132") (name "DB4-1") (class "Default")
      (node (ref "IC21") (pin "4") (pinfunction "A2_4") (pintype "input"))
      (node (ref "U$8") (pin "Z") (pinfunction "1_Z") (pintype "bidirectional"))
    )
    (net (code "133") (name "DB4-2") (class "Default")
      (node (ref "IC23") (pin "4") (pinfunction "A2_4") (pintype "input"))
      (node (ref "U$9") (pin "Z") (pinfunction "1_Z") (pintype "bidirectional"))
    )
    (net (code "134") (name "DB4-3") (class "Default")
      (node (ref "IC25") (pin "4") (pinfunction "A2_4") (pintype "input"))
      (node (ref "U$10") (pin "Z") (pinfunction "1_Z") (pintype "bidirectional"))
    )
    (net (code "135") (name "DB5") (class "Default")
      (node (ref "E2") (pin "15") (pinfunction "B_15") (pintype "bidirectional"))
      (node (ref "U$6") (pin "DD") (pinfunction "1_DD") (pintype "bidirectional"))
    )
    (net (code "136") (name "DB5-0") (class "Default")
      (node (ref "IC19") (pin "6") (pinfunction "A3_6") (pintype "input"))
      (node (ref "U$7") (pin "DD") (pinfunction "1_DD") (pintype "bidirectional"))
    )
    (net (code "137") (name "DB5-1") (class "Default")
      (node (ref "IC21") (pin "6") (pinfunction "A3_6") (pintype "input"))
      (node (ref "U$8") (pin "DD") (pinfunction "1_DD") (pintype "bidirectional"))
    )
    (net (code "138") (name "DB5-2") (class "Default")
      (node (ref "IC23") (pin "6") (pinfunction "A3_6") (pintype "input"))
      (node (ref "U$9") (pin "DD") (pinfunction "1_DD") (pintype "bidirectional"))
    )
    (net (code "139") (name "DB5-3") (class "Default")
      (node (ref "IC25") (pin "6") (pinfunction "A3_6") (pintype "input"))
      (node (ref "U$10") (pin "DD") (pinfunction "1_DD") (pintype "bidirectional"))
    )
    (net (code "140") (name "DB6") (class "Default")
      (node (ref "E2") (pin "2") (pinfunction "B_2") (pintype "bidirectional"))
      (node (ref "U$6") (pin "JJ") (pinfunction "1_JJ") (pintype "bidirectional"))
    )
    (net (code "141") (name "DB6-0") (class "Default")
      (node (ref "IC19") (pin "13") (pinfunction "A2_13") (pintype "input"))
      (node (ref "U$7") (pin "JJ") (pinfunction "1_JJ") (pintype "bidirectional"))
    )
    (net (code "142") (name "DB6-1") (class "Default")
      (node (ref "IC21") (pin "13") (pinfunction "A2_13") (pintype "input"))
      (node (ref "U$8") (pin "JJ") (pinfunction "1_JJ") (pintype "bidirectional"))
    )
    (net (code "143") (name "DB6-2") (class "Default")
      (node (ref "IC23") (pin "13") (pinfunction "A2_13") (pintype "input"))
      (node (ref "U$9") (pin "JJ") (pinfunction "1_JJ") (pintype "bidirectional"))
    )
    (net (code "144") (name "DB6-3") (class "Default")
      (node (ref "IC25") (pin "13") (pinfunction "A2_13") (pintype "input"))
      (node (ref "U$10") (pin "JJ") (pinfunction "1_JJ") (pintype "bidirectional"))
    )
    (net (code "145") (name "DB7") (class "Default")
      (node (ref "E2") (pin "9") (pinfunction "B_9") (pintype "bidirectional"))
      (node (ref "U$6") (pin "NN") (pinfunction "1_NN") (pintype "bidirectional"))
    )
    (net (code "146") (name "DB7-0") (class "Default")
      (node (ref "IC19") (pin "8") (pinfunction "A4_8") (pintype "input"))
      (node (ref "U$7") (pin "NN") (pinfunction "1_NN") (pintype "bidirectional"))
    )
    (net (code "147") (name "DB7-1") (class "Default")
      (node (ref "IC21") (pin "8") (pinfunction "A4_8") (pintype "input"))
      (node (ref "U$8") (pin "NN") (pinfunction "1_NN") (pintype "bidirectional"))
    )
    (net (code "148") (name "DB7-2") (class "Default")
      (node (ref "IC23") (pin "8") (pinfunction "A4_8") (pintype "input"))
      (node (ref "U$9") (pin "NN") (pinfunction "1_NN") (pintype "bidirectional"))
    )
    (net (code "149") (name "DB7-3") (class "Default")
      (node (ref "IC25") (pin "8") (pinfunction "A4_8") (pintype "input"))
      (node (ref "U$10") (pin "NN") (pinfunction "1_NN") (pintype "bidirectional"))
    )
    (net (code "150") (name "DB8") (class "Default")
      (node (ref "E2") (pin "7") (pinfunction "B_7") (pintype "bidirectional"))
      (node (ref "U$6") (pin "TT") (pinfunction "1_TT") (pintype "bidirectional"))
    )
    (net (code "151") (name "DB8-0") (class "Default")
      (node (ref "IC19") (pin "11") (pinfunction "A1_11") (pintype "input"))
      (node (ref "U$7") (pin "TT") (pinfunction "1_TT") (pintype "bidirectional"))
    )
    (net (code "152") (name "DB8-1") (class "Default")
      (node (ref "IC21") (pin "11") (pinfunction "A1_11") (pintype "input"))
      (node (ref "U$8") (pin "TT") (pinfunction "1_TT") (pintype "bidirectional"))
    )
    (net (code "153") (name "DB8-2") (class "Default")
      (node (ref "IC23") (pin "11") (pinfunction "A1_11") (pintype "input"))
      (node (ref "U$9") (pin "TT") (pinfunction "1_TT") (pintype "bidirectional"))
    )
    (net (code "154") (name "DB8-3") (class "Default")
      (node (ref "IC25") (pin "11") (pinfunction "A1_11") (pintype "input"))
      (node (ref "U$10") (pin "TT") (pinfunction "1_TT") (pintype "bidirectional"))
    )
    (net (code "155") (name "DB9") (class "Default")
      (node (ref "E4") (pin "2") (pinfunction "B_2") (pintype "bidirectional"))
      (node (ref "U$6") (pin "D") (pinfunction "1_D") (pintype "bidirectional"))
    )
    (net (code "156") (name "DB9-0") (class "Default")
      (node (ref "IC20") (pin "2") (pinfunction "A1_2") (pintype "input"))
      (node (ref "U$7") (pin "D") (pinfunction "1_D") (pintype "bidirectional"))
    )
    (net (code "157") (name "DB9-1") (class "Default")
      (node (ref "IC22") (pin "2") (pinfunction "A1_2") (pintype "input"))
      (node (ref "U$8") (pin "D") (pinfunction "1_D") (pintype "bidirectional"))
    )
    (net (code "158") (name "DB9-2") (class "Default")
      (node (ref "IC24") (pin "2") (pinfunction "A1_2") (pintype "input"))
      (node (ref "U$9") (pin "D") (pinfunction "1_D") (pintype "bidirectional"))
    )
    (net (code "159") (name "DB9-3") (class "Default")
      (node (ref "IC26") (pin "2") (pinfunction "A1_2") (pintype "input"))
      (node (ref "U$10") (pin "D") (pinfunction "1_D") (pintype "bidirectional"))
    )
    (net (code "160") (name "DB10") (class "Default")
      (node (ref "E4") (pin "7") (pinfunction "B_7") (pintype "bidirectional"))
      (node (ref "U$6") (pin "J") (pinfunction "1_J") (pintype "bidirectional"))
    )
    (net (code "161") (name "DB10-0") (class "Default")
      (node (ref "IC20") (pin "6") (pinfunction "A3_6") (pintype "input"))
      (node (ref "U$7") (pin "J") (pinfunction "1_J") (pintype "bidirectional"))
    )
    (net (code "162") (name "DB10-1") (class "Default")
      (node (ref "IC22") (pin "6") (pinfunction "A3_6") (pintype "input"))
      (node (ref "U$8") (pin "J") (pinfunction "1_J") (pintype "bidirectional"))
    )
    (net (code "163") (name "DB10-2") (class "Default")
      (node (ref "IC24") (pin "6") (pinfunction "A3_6") (pintype "input"))
      (node (ref "U$9") (pin "J") (pinfunction "1_J") (pintype "bidirectional"))
    )
    (net (code "164") (name "DB10-3") (class "Default")
      (node (ref "IC26") (pin "6") (pinfunction "A3_6") (pintype "input"))
      (node (ref "U$10") (pin "J") (pinfunction "1_J") (pintype "bidirectional"))
    )
    (net (code "165") (name "DB11") (class "Default")
      (node (ref "E3") (pin "15") (pinfunction "B_15") (pintype "bidirectional"))
      (node (ref "U$6") (pin "N") (pinfunction "1_N") (pintype "bidirectional"))
    )
    (net (code "166") (name "DB11-0") (class "Default")
      (node (ref "IC19") (pin "17") (pinfunction "A4_17") (pintype "input"))
      (node (ref "U$7") (pin "N") (pinfunction "1_N") (pintype "bidirectional"))
    )
    (net (code "167") (name "DB11-1") (class "Default")
      (node (ref "IC21") (pin "17") (pinfunction "A4_17") (pintype "input"))
      (node (ref "U$8") (pin "N") (pinfunction "1_N") (pintype "bidirectional"))
    )
    (net (code "168") (name "DB11-2") (class "Default")
      (node (ref "IC23") (pin "17") (pinfunction "A4_17") (pintype "input"))
      (node (ref "U$9") (pin "N") (pinfunction "1_N") (pintype "bidirectional"))
    )
    (net (code "169") (name "DB11-3") (class "Default")
      (node (ref "IC25") (pin "17") (pinfunction "A4_17") (pintype "input"))
      (node (ref "U$10") (pin "N") (pinfunction "1_N") (pintype "bidirectional"))
    )
    (net (code "170") (name "DB_EN0") (class "Default")
      (node (ref "IC19") (pin "1") (pinfunction "G_1") (pintype "input"))
      (node (ref "IC19") (pin "19") (pinfunction "G_19") (pintype "input"))
      (node (ref "IC20") (pin "1") (pinfunction "G_1") (pintype "input"))
      (node (ref "IC20") (pin "19") (pinfunction "G_19") (pintype "input"))
      (node (ref "SV2") (pin "10") (pinfunction "10_10") (pintype "passive"))
    )
    (net (code "171") (name "DB_EN1") (class "Default")
      (node (ref "IC21") (pin "1") (pinfunction "G_1") (pintype "input"))
      (node (ref "IC21") (pin "19") (pinfunction "G_19") (pintype "input"))
      (node (ref "IC22") (pin "1") (pinfunction "G_1") (pintype "input"))
      (node (ref "IC22") (pin "19") (pinfunction "G_19") (pintype "input"))
      (node (ref "SV2") (pin "8") (pinfunction "8_8") (pintype "passive"))
    )
    (net (code "172") (name "DB_EN2") (class "Default")
      (node (ref "IC23") (pin "1") (pinfunction "G_1") (pintype "input"))
      (node (ref "IC23") (pin "19") (pinfunction "G_19") (pintype "input"))
      (node (ref "IC24") (pin "1") (pinfunction "G_1") (pintype "input"))
      (node (ref "IC24") (pin "19") (pinfunction "G_19") (pintype "input"))
      (node (ref "SV2") (pin "6") (pinfunction "6_6") (pintype "passive"))
    )
    (net (code "173") (name "DB_EN3") (class "Default")
      (node (ref "IC25") (pin "1") (pinfunction "G_1") (pintype "input"))
      (node (ref "IC25") (pin "19") (pinfunction "G_19") (pintype "input"))
      (node (ref "IC26") (pin "1") (pinfunction "G_1") (pintype "input"))
      (node (ref "IC26") (pin "19") (pinfunction "G_19") (pintype "input"))
      (node (ref "SV2") (pin "4") (pinfunction "4_4") (pintype "passive"))
    )
    (net (code "174") (name "GND") (class "Default")
      (node (ref "IC20") (pin "15") (pinfunction "A3_15") (pintype "input"))
      (node (ref "IC20") (pin "17") (pinfunction "A4_17") (pintype "input"))
      (node (ref "IC22") (pin "15") (pinfunction "A3_15") (pintype "input"))
      (node (ref "IC22") (pin "17") (pinfunction "A4_17") (pintype "input"))
      (node (ref "IC24") (pin "15") (pinfunction "A3_15") (pintype "input"))
      (node (ref "IC24") (pin "17") (pinfunction "A4_17") (pintype "input"))
      (node (ref "IC26") (pin "15") (pinfunction "A3_15") (pintype "input"))
      (node (ref "IC26") (pin "17") (pinfunction "A4_17") (pintype "input"))
      (node (ref "SV2") (pin "19") (pinfunction "19_19") (pintype "passive"))
      (node (ref "SV2") (pin "2") (pinfunction "2_2") (pintype "passive"))
    )
    (net (code "175") (name "INC_MB") (class "Default")
      (node (ref "U$1") (pin "LL") (pinfunction "1_LL") (pintype "bidirectional"))
      (node (ref "U$2") (pin "LL") (pinfunction "1_LL") (pintype "bidirectional"))
      (node (ref "U$3") (pin "LL") (pinfunction "1_LL") (pintype "bidirectional"))
      (node (ref "U$4") (pin "LL") (pinfunction "1_LL") (pintype "bidirectional"))
      (node (ref "U$5") (pin "LL") (pinfunction "1_LL") (pintype "bidirectional"))
    )
    (net (code "176") (name "INITALIZE") (class "Default")
      (node (ref "U$1") (pin "RR") (pinfunction "1_RR") (pintype "bidirectional"))
      (node (ref "U$2") (pin "RR") (pinfunction "1_RR") (pintype "bidirectional"))
      (node (ref "U$3") (pin "RR") (pinfunction "1_RR") (pintype "bidirectional"))
      (node (ref "U$4") (pin "RR") (pinfunction "1_RR") (pintype "bidirectional"))
      (node (ref "U$5") (pin "RR") (pinfunction "1_RR") (pintype "bidirectional"))
    )
    (net (code "177") (name "VCC") (class "Default")
      (node (ref "E1") (pin "12") (pinfunction "TXD_12") (pintype "input"))
      (node (ref "E16") (pin "12") (pinfunction "TXD_12") (pintype "input"))
      (node (ref "E17") (pin "12") (pinfunction "TXD_12") (pintype "input"))
      (node (ref "E18") (pin "12") (pinfunction "TXD_12") (pintype "input"))
      (node (ref "E2") (pin "12") (pinfunction "TXD_12") (pintype "input"))
      (node (ref "E3") (pin "12") (pinfunction "TXD_12") (pintype "input"))
      (node (ref "E4") (pin "12") (pinfunction "TXD_12") (pintype "input"))
      (node (ref "E5") (pin "12") (pinfunction "TXD_12") (pintype "input"))
      (node (ref "SV2") (pin "1") (pinfunction "1_1") (pintype "passive"))
      (node (ref "SV2") (pin "20") (pinfunction "20_20") (pintype "passive"))
    )
    (net (code "178") (name "WCOV") (class "Default")
      (node (ref "U$6") (pin "BB") (pinfunction "1_BB") (pintype "bidirectional"))
    )
    (net (code "179") (name "WCOV0") (class "Default")
      (node (ref "U$7") (pin "BB") (pinfunction "1_BB") (pintype "bidirectional"))
    )
    (net (code "180") (name "WCOV1") (class "Default")
      (node (ref "U$8") (pin "BB") (pinfunction "1_BB") (pintype "bidirectional"))
    )
    (net (code "181") (name "WCOV2") (class "Default")
      (node (ref "U$9") (pin "BB") (pinfunction "1_BB") (pintype "bidirectional"))
    )
    (net (code "182") (name "WCOV3") (class "Default")
      (node (ref "U$10") (pin "BB") (pinfunction "1_BB") (pintype "bidirectional"))
    )
    (net (code "183") (name "unconnected-(E1A-R-Pad3)") (class "Default")
      (node (ref "E1") (pin "3") (pinfunction "R_3") (pintype "output"))
    )
    (net (code "184") (name "unconnected-(E1B-R-Pad6)") (class "Default")
      (node (ref "E1") (pin "6") (pinfunction "R_6") (pintype "output"))
    )
    (net (code "185") (name "unconnected-(E1C-R-Pad10)") (class "Default")
      (node (ref "E1") (pin "10") (pinfunction "R_10") (pintype "output"))
    )
    (net (code "186") (name "unconnected-(E1D-R-Pad14)") (class "Default")
      (node (ref "E1") (pin "14") (pinfunction "R_14") (pintype "output"))
    )
    (net (code "187") (name "unconnected-(E2A-R-Pad3)") (class "Default")
      (node (ref "E2") (pin "3") (pinfunction "R_3") (pintype "output"))
    )
    (net (code "188") (name "unconnected-(E2B-R-Pad6)") (class "Default")
      (node (ref "E2") (pin "6") (pinfunction "R_6") (pintype "output"))
    )
    (net (code "189") (name "unconnected-(E2C-R-Pad10)") (class "Default")
      (node (ref "E2") (pin "10") (pinfunction "R_10") (pintype "output"))
    )
    (net (code "190") (name "unconnected-(E2D-R-Pad14)") (class "Default")
      (node (ref "E2") (pin "14") (pinfunction "R_14") (pintype "output"))
    )
    (net (code "191") (name "unconnected-(E3A-R-Pad3)") (class "Default")
      (node (ref "E3") (pin "3") (pinfunction "R_3") (pintype "output"))
    )
    (net (code "192") (name "unconnected-(E3B-R-Pad6)") (class "Default")
      (node (ref "E3") (pin "6") (pinfunction "R_6") (pintype "output"))
    )
    (net (code "193") (name "unconnected-(E3C-R-Pad10)") (class "Default")
      (node (ref "E3") (pin "10") (pinfunction "R_10") (pintype "output"))
    )
    (net (code "194") (name "unconnected-(E3D-R-Pad14)") (class "Default")
      (node (ref "E3") (pin "14") (pinfunction "R_14") (pintype "output"))
    )
    (net (code "195") (name "unconnected-(E4A-R-Pad3)") (class "Default")
      (node (ref "E4") (pin "3") (pinfunction "R_3") (pintype "output"))
    )
    (net (code "196") (name "unconnected-(E4B-R-Pad6)") (class "Default")
      (node (ref "E4") (pin "6") (pinfunction "R_6") (pintype "output"))
    )
    (net (code "197") (name "unconnected-(E4C-R-Pad10)") (class "Default")
      (node (ref "E4") (pin "10") (pinfunction "R_10") (pintype "output"))
    )
    (net (code "198") (name "unconnected-(E4D-R-Pad14)") (class "Default")
      (node (ref "E4") (pin "14") (pinfunction "R_14") (pintype "output"))
    )
    (net (code "199") (name "unconnected-(E5A-R-Pad3)") (class "Default")
      (node (ref "E5") (pin "3") (pinfunction "R_3") (pintype "output"))
    )
    (net (code "200") (name "unconnected-(E5B-R-Pad6)") (class "Default")
      (node (ref "E5") (pin "6") (pinfunction "R_6") (pintype "output"))
    )
    (net (code "201") (name "unconnected-(E16A-R-Pad3)") (class "Default")
      (node (ref "E16") (pin "3") (pinfunction "R_3") (pintype "output"))
    )
    (net (code "202") (name "unconnected-(E16B-R-Pad6)") (class "Default")
      (node (ref "E16") (pin "6") (pinfunction "R_6") (pintype "output"))
    )
    (net (code "203") (name "unconnected-(E16C-R-Pad10)") (class "Default")
      (node (ref "E16") (pin "10") (pinfunction "R_10") (pintype "output"))
    )
    (net (code "204") (name "unconnected-(E16D-R-Pad14)") (class "Default")
      (node (ref "E16") (pin "14") (pinfunction "R_14") (pintype "output"))
    )
    (net (code "205") (name "unconnected-(E17A-R-Pad3)") (class "Default")
      (node (ref "E17") (pin "3") (pinfunction "R_3") (pintype "output"))
    )
    (net (code "206") (name "unconnected-(E17B-R-Pad6)") (class "Default")
      (node (ref "E17") (pin "6") (pinfunction "R_6") (pintype "output"))
    )
    (net (code "207") (name "unconnected-(E17C-R-Pad10)") (class "Default")
      (node (ref "E17") (pin "10") (pinfunction "R_10") (pintype "output"))
    )
    (net (code "208") (name "unconnected-(E17D-R-Pad14)") (class "Default")
      (node (ref "E17") (pin "14") (pinfunction "R_14") (pintype "output"))
    )
    (net (code "209") (name "unconnected-(E18A-R-Pad3)") (class "Default")
      (node (ref "E18") (pin "3") (pinfunction "R_3") (pintype "output"))
    )
    (net (code "210") (name "unconnected-(E18B-R-Pad6)") (class "Default")
      (node (ref "E18") (pin "6") (pinfunction "R_6") (pintype "output"))
    )
    (net (code "211") (name "unconnected-(E18C-R-Pad10)") (class "Default")
      (node (ref "E18") (pin "10") (pinfunction "R_10") (pintype "output"))
    )
    (net (code "212") (name "unconnected-(E18D-R-Pad14)") (class "Default")
      (node (ref "E18") (pin "14") (pinfunction "R_14") (pintype "output"))
    )
    (net (code "213") (name "unconnected-(IC20B-Y3-Pad5)") (class "Default")
      (node (ref "IC20") (pin "5") (pinfunction "Y3_5") (pintype "tri_state"))
    )
    (net (code "214") (name "unconnected-(IC20B-Y4-Pad3)") (class "Default")
      (node (ref "IC20") (pin "3") (pinfunction "Y4_3") (pintype "tri_state"))
    )
    (net (code "215") (name "unconnected-(IC22B-Y3-Pad5)") (class "Default")
      (node (ref "IC22") (pin "5") (pinfunction "Y3_5") (pintype "tri_state"))
    )
    (net (code "216") (name "unconnected-(IC22B-Y4-Pad3)") (class "Default")
      (node (ref "IC22") (pin "3") (pinfunction "Y4_3") (pintype "tri_state"))
    )
    (net (code "217") (name "unconnected-(IC24B-Y3-Pad5)") (class "Default")
      (node (ref "IC24") (pin "5") (pinfunction "Y3_5") (pintype "tri_state"))
    )
    (net (code "218") (name "unconnected-(IC24B-Y4-Pad3)") (class "Default")
      (node (ref "IC24") (pin "3") (pinfunction "Y4_3") (pintype "tri_state"))
    )
    (net (code "219") (name "unconnected-(IC26B-Y3-Pad5)") (class "Default")
      (node (ref "IC26") (pin "5") (pinfunction "Y3_5") (pintype "tri_state"))
    )
    (net (code "220") (name "unconnected-(IC26B-Y4-Pad3)") (class "Default")
      (node (ref "IC26") (pin "3") (pinfunction "Y4_3") (pintype "tri_state"))
    )
    (net (code "221") (name "~{1-CA_INH}") (class "Default")
      (node (ref "E5") (pin "5") (pinfunction "D_5") (pintype "input"))
      (node (ref "IC20") (pin "9") (pinfunction "Y1_9") (pintype "tri_state"))
      (node (ref "IC22") (pin "9") (pinfunction "Y1_9") (pintype "tri_state"))
      (node (ref "IC24") (pin "9") (pinfunction "Y1_9") (pintype "tri_state"))
      (node (ref "IC26") (pin "9") (pinfunction "Y1_9") (pintype "tri_state"))
    )
    (net (code "222") (name "~{CYC_SEL}") (class "Default")
      (node (ref "E1") (pin "11") (pinfunction "D_11") (pintype "input"))
      (node (ref "IC12") (pin "9") (pinfunction "Y1_9") (pintype "tri_state"))
      (node (ref "IC14") (pin "9") (pinfunction "Y1_9") (pintype "tri_state"))
      (node (ref "IC16") (pin "9") (pinfunction "Y1_9") (pintype "tri_state"))
      (node (ref "IC18") (pin "9") (pinfunction "Y1_9") (pintype "tri_state"))
    )
    (net (code "223") (name "~{DA0}") (class "Default")
      (node (ref "E18") (pin "13") (pinfunction "D_13") (pintype "input"))
      (node (ref "IC12") (pin "16") (pinfunction "Y2_16") (pintype "tri_state"))
      (node (ref "IC14") (pin "16") (pinfunction "Y2_16") (pintype "tri_state"))
      (node (ref "IC16") (pin "16") (pinfunction "Y2_16") (pintype "tri_state"))
      (node (ref "IC18") (pin "16") (pinfunction "Y2_16") (pintype "tri_state"))
    )
    (net (code "224") (name "~{DA1}") (class "Default")
      (node (ref "E18") (pin "11") (pinfunction "D_11") (pintype "input"))
      (node (ref "IC12") (pin "12") (pinfunction "Y4_12") (pintype "tri_state"))
      (node (ref "IC14") (pin "12") (pinfunction "Y4_12") (pintype "tri_state"))
      (node (ref "IC16") (pin "12") (pinfunction "Y4_12") (pintype "tri_state"))
      (node (ref "IC18") (pin "12") (pinfunction "Y4_12") (pintype "tri_state"))
    )
    (net (code "225") (name "~{DA2}") (class "Default")
      (node (ref "E17") (pin "4") (pinfunction "D_4") (pintype "input"))
      (node (ref "IC11") (pin "5") (pinfunction "Y3_5") (pintype "tri_state"))
      (node (ref "IC13") (pin "5") (pinfunction "Y3_5") (pintype "tri_state"))
      (node (ref "IC15") (pin "5") (pinfunction "Y3_5") (pintype "tri_state"))
      (node (ref "IC17") (pin "5") (pinfunction "Y3_5") (pintype "tri_state"))
    )
    (net (code "226") (name "~{DA3}") (class "Default")
      (node (ref "E17") (pin "11") (pinfunction "D_11") (pintype "input"))
      (node (ref "IC11") (pin "18") (pinfunction "Y1_18") (pintype "tri_state"))
      (node (ref "IC13") (pin "18") (pinfunction "Y1_18") (pintype "tri_state"))
      (node (ref "IC15") (pin "18") (pinfunction "Y1_18") (pintype "tri_state"))
      (node (ref "IC17") (pin "18") (pinfunction "Y1_18") (pintype "tri_state"))
    )
    (net (code "227") (name "~{DA4}") (class "Default")
      (node (ref "E17") (pin "5") (pinfunction "D_5") (pintype "input"))
      (node (ref "IC11") (pin "16") (pinfunction "Y2_16") (pintype "tri_state"))
      (node (ref "IC13") (pin "16") (pinfunction "Y2_16") (pintype "tri_state"))
      (node (ref "IC15") (pin "16") (pinfunction "Y2_16") (pintype "tri_state"))
      (node (ref "IC17") (pin "16") (pinfunction "Y2_16") (pintype "tri_state"))
    )
    (net (code "228") (name "~{DA5}") (class "Default")
      (node (ref "E16") (pin "13") (pinfunction "D_13") (pintype "input"))
      (node (ref "IC11") (pin "14") (pinfunction "Y3_14") (pintype "tri_state"))
      (node (ref "IC13") (pin "14") (pinfunction "Y3_14") (pintype "tri_state"))
      (node (ref "IC15") (pin "14") (pinfunction "Y3_14") (pintype "tri_state"))
      (node (ref "IC17") (pin "14") (pinfunction "Y3_14") (pintype "tri_state"))
    )
    (net (code "229") (name "~{DA6}") (class "Default")
      (node (ref "E16") (pin "4") (pinfunction "D_4") (pintype "input"))
      (node (ref "IC11") (pin "7") (pinfunction "Y2_7") (pintype "tri_state"))
      (node (ref "IC13") (pin "7") (pinfunction "Y2_7") (pintype "tri_state"))
      (node (ref "IC15") (pin "7") (pinfunction "Y2_7") (pintype "tri_state"))
      (node (ref "IC17") (pin "7") (pinfunction "Y2_7") (pintype "tri_state"))
    )
    (net (code "230") (name "~{DA7}") (class "Default")
      (node (ref "E16") (pin "11") (pinfunction "D_11") (pintype "input"))
      (node (ref "IC11") (pin "12") (pinfunction "Y4_12") (pintype "tri_state"))
      (node (ref "IC13") (pin "12") (pinfunction "Y4_12") (pintype "tri_state"))
      (node (ref "IC15") (pin "12") (pinfunction "Y4_12") (pintype "tri_state"))
      (node (ref "IC17") (pin "12") (pinfunction "Y4_12") (pintype "tri_state"))
    )
    (net (code "231") (name "~{DA8}") (class "Default")
      (node (ref "E16") (pin "5") (pinfunction "D_5") (pintype "input"))
      (node (ref "IC11") (pin "9") (pinfunction "Y1_9") (pintype "tri_state"))
      (node (ref "IC13") (pin "9") (pinfunction "Y1_9") (pintype "tri_state"))
      (node (ref "IC15") (pin "9") (pinfunction "Y1_9") (pintype "tri_state"))
      (node (ref "IC17") (pin "9") (pinfunction "Y1_9") (pintype "tri_state"))
    )
    (net (code "232") (name "~{DA9}") (class "Default")
      (node (ref "E18") (pin "4") (pinfunction "D_4") (pintype "input"))
      (node (ref "IC12") (pin "18") (pinfunction "Y1_18") (pintype "tri_state"))
      (node (ref "IC14") (pin "18") (pinfunction "Y1_18") (pintype "tri_state"))
      (node (ref "IC16") (pin "18") (pinfunction "Y1_18") (pintype "tri_state"))
      (node (ref "IC18") (pin "18") (pinfunction "Y1_18") (pintype "tri_state"))
    )
    (net (code "233") (name "~{DA10}") (class "Default")
      (node (ref "E18") (pin "5") (pinfunction "D_5") (pintype "input"))
      (node (ref "IC12") (pin "14") (pinfunction "Y3_14") (pintype "tri_state"))
      (node (ref "IC14") (pin "14") (pinfunction "Y3_14") (pintype "tri_state"))
      (node (ref "IC16") (pin "14") (pinfunction "Y3_14") (pintype "tri_state"))
      (node (ref "IC18") (pin "14") (pinfunction "Y3_14") (pintype "tri_state"))
    )
    (net (code "234") (name "~{DA11}") (class "Default")
      (node (ref "E17") (pin "13") (pinfunction "D_13") (pintype "input"))
      (node (ref "IC11") (pin "3") (pinfunction "Y4_3") (pintype "tri_state"))
      (node (ref "IC13") (pin "3") (pinfunction "Y4_3") (pintype "tri_state"))
      (node (ref "IC15") (pin "3") (pinfunction "Y4_3") (pintype "tri_state"))
      (node (ref "IC17") (pin "3") (pinfunction "Y4_3") (pintype "tri_state"))
    )
    (net (code "235") (name "~{DAEX0}") (class "Default")
      (node (ref "E1") (pin "5") (pinfunction "D_5") (pintype "input"))
      (node (ref "IC12") (pin "7") (pinfunction "Y2_7") (pintype "tri_state"))
      (node (ref "IC14") (pin "7") (pinfunction "Y2_7") (pintype "tri_state"))
      (node (ref "IC16") (pin "7") (pinfunction "Y2_7") (pintype "tri_state"))
      (node (ref "IC18") (pin "7") (pinfunction "Y2_7") (pintype "tri_state"))
    )
    (net (code "236") (name "~{DAEX1}") (class "Default")
      (node (ref "E1") (pin "13") (pinfunction "D_13") (pintype "input"))
      (node (ref "IC12") (pin "5") (pinfunction "Y3_5") (pintype "tri_state"))
      (node (ref "IC14") (pin "5") (pinfunction "Y3_5") (pintype "tri_state"))
      (node (ref "IC16") (pin "5") (pinfunction "Y3_5") (pintype "tri_state"))
      (node (ref "IC18") (pin "5") (pinfunction "Y3_5") (pintype "tri_state"))
    )
    (net (code "237") (name "~{DAEX2}") (class "Default")
      (node (ref "E1") (pin "4") (pinfunction "D_4") (pintype "input"))
      (node (ref "IC12") (pin "3") (pinfunction "Y4_3") (pintype "tri_state"))
      (node (ref "IC14") (pin "3") (pinfunction "Y4_3") (pintype "tri_state"))
      (node (ref "IC16") (pin "3") (pinfunction "Y4_3") (pintype "tri_state"))
      (node (ref "IC18") (pin "3") (pinfunction "Y4_3") (pintype "tri_state"))
    )
    (net (code "238") (name "~{DATA_OUT}") (class "Default")
      (node (ref "E5") (pin "4") (pinfunction "D_4") (pintype "input"))
      (node (ref "IC20") (pin "7") (pinfunction "Y2_7") (pintype "tri_state"))
      (node (ref "IC22") (pin "7") (pinfunction "Y2_7") (pintype "tri_state"))
      (node (ref "IC24") (pin "7") (pinfunction "Y2_7") (pintype "tri_state"))
      (node (ref "IC26") (pin "7") (pinfunction "Y2_7") (pintype "tri_state"))
    )
    (net (code "239") (name "~{DB0}") (class "Default")
      (node (ref "E4") (pin "13") (pinfunction "D_13") (pintype "input"))
      (node (ref "IC20") (pin "16") (pinfunction "Y2_16") (pintype "tri_state"))
      (node (ref "IC22") (pin "16") (pinfunction "Y2_16") (pintype "tri_state"))
      (node (ref "IC24") (pin "16") (pinfunction "Y2_16") (pintype "tri_state"))
      (node (ref "IC26") (pin "16") (pinfunction "Y2_16") (pintype "tri_state"))
    )
    (net (code "240") (name "~{DB1}") (class "Default")
      (node (ref "E4") (pin "11") (pinfunction "D_11") (pintype "input"))
      (node (ref "IC20") (pin "12") (pinfunction "Y4_12") (pintype "tri_state"))
      (node (ref "IC22") (pin "12") (pinfunction "Y4_12") (pintype "tri_state"))
      (node (ref "IC24") (pin "12") (pinfunction "Y4_12") (pintype "tri_state"))
      (node (ref "IC26") (pin "12") (pinfunction "Y4_12") (pintype "tri_state"))
    )
    (net (code "241") (name "~{DB2}") (class "Default")
      (node (ref "E3") (pin "4") (pinfunction "D_4") (pintype "input"))
      (node (ref "IC19") (pin "5") (pinfunction "Y3_5") (pintype "tri_state"))
      (node (ref "IC21") (pin "5") (pinfunction "Y3_5") (pintype "tri_state"))
      (node (ref "IC23") (pin "5") (pinfunction "Y3_5") (pintype "tri_state"))
      (node (ref "IC25") (pin "5") (pinfunction "Y3_5") (pintype "tri_state"))
    )
    (net (code "242") (name "~{DB3}") (class "Default")
      (node (ref "E3") (pin "11") (pinfunction "D_11") (pintype "input"))
      (node (ref "IC19") (pin "18") (pinfunction "Y1_18") (pintype "tri_state"))
      (node (ref "IC21") (pin "18") (pinfunction "Y1_18") (pintype "tri_state"))
      (node (ref "IC23") (pin "18") (pinfunction "Y1_18") (pintype "tri_state"))
      (node (ref "IC25") (pin "18") (pinfunction "Y1_18") (pintype "tri_state"))
    )
    (net (code "243") (name "~{DB4}") (class "Default")
      (node (ref "E3") (pin "5") (pinfunction "D_5") (pintype "input"))
      (node (ref "IC19") (pin "16") (pinfunction "Y2_16") (pintype "tri_state"))
      (node (ref "IC21") (pin "16") (pinfunction "Y2_16") (pintype "tri_state"))
      (node (ref "IC23") (pin "16") (pinfunction "Y2_16") (pintype "tri_state"))
      (node (ref "IC25") (pin "16") (pinfunction "Y2_16") (pintype "tri_state"))
    )
    (net (code "244") (name "~{DB5}") (class "Default")
      (node (ref "E2") (pin "13") (pinfunction "D_13") (pintype "input"))
      (node (ref "IC19") (pin "14") (pinfunction "Y3_14") (pintype "tri_state"))
      (node (ref "IC21") (pin "14") (pinfunction "Y3_14") (pintype "tri_state"))
      (node (ref "IC23") (pin "14") (pinfunction "Y3_14") (pintype "tri_state"))
      (node (ref "IC25") (pin "14") (pinfunction "Y3_14") (pintype "tri_state"))
    )
    (net (code "245") (name "~{DB6}") (class "Default")
      (node (ref "E2") (pin "4") (pinfunction "D_4") (pintype "input"))
      (node (ref "IC19") (pin "7") (pinfunction "Y2_7") (pintype "tri_state"))
      (node (ref "IC21") (pin "7") (pinfunction "Y2_7") (pintype "tri_state"))
      (node (ref "IC23") (pin "7") (pinfunction "Y2_7") (pintype "tri_state"))
      (node (ref "IC25") (pin "7") (pinfunction "Y2_7") (pintype "tri_state"))
    )
    (net (code "246") (name "~{DB7}") (class "Default")
      (node (ref "E2") (pin "11") (pinfunction "D_11") (pintype "input"))
      (node (ref "IC19") (pin "12") (pinfunction "Y4_12") (pintype "tri_state"))
      (node (ref "IC21") (pin "12") (pinfunction "Y4_12") (pintype "tri_state"))
      (node (ref "IC23") (pin "12") (pinfunction "Y4_12") (pintype "tri_state"))
      (node (ref "IC25") (pin "12") (pinfunction "Y4_12") (pintype "tri_state"))
    )
    (net (code "247") (name "~{DB8}") (class "Default")
      (node (ref "E2") (pin "5") (pinfunction "D_5") (pintype "input"))
      (node (ref "IC19") (pin "9") (pinfunction "Y1_9") (pintype "tri_state"))
      (node (ref "IC21") (pin "9") (pinfunction "Y1_9") (pintype "tri_state"))
      (node (ref "IC23") (pin "9") (pinfunction "Y1_9") (pintype "tri_state"))
      (node (ref "IC25") (pin "9") (pinfunction "Y1_9") (pintype "tri_state"))
    )
    (net (code "248") (name "~{DB9}") (class "Default")
      (node (ref "E4") (pin "4") (pinfunction "D_4") (pintype "input"))
      (node (ref "IC20") (pin "18") (pinfunction "Y1_18") (pintype "tri_state"))
      (node (ref "IC22") (pin "18") (pinfunction "Y1_18") (pintype "tri_state"))
      (node (ref "IC24") (pin "18") (pinfunction "Y1_18") (pintype "tri_state"))
      (node (ref "IC26") (pin "18") (pinfunction "Y1_18") (pintype "tri_state"))
    )
    (net (code "249") (name "~{DB10}") (class "Default")
      (node (ref "E4") (pin "5") (pinfunction "D_5") (pintype "input"))
      (node (ref "IC20") (pin "14") (pinfunction "Y3_14") (pintype "tri_state"))
      (node (ref "IC22") (pin "14") (pinfunction "Y3_14") (pintype "tri_state"))
      (node (ref "IC24") (pin "14") (pinfunction "Y3_14") (pintype "tri_state"))
      (node (ref "IC26") (pin "14") (pinfunction "Y3_14") (pintype "tri_state"))
    )
    (net (code "250") (name "~{DB11}") (class "Default")
      (node (ref "E3") (pin "13") (pinfunction "D_13") (pintype "input"))
      (node (ref "IC19") (pin "3") (pinfunction "Y4_3") (pintype "tri_state"))
      (node (ref "IC21") (pin "3") (pinfunction "Y4_3") (pintype "tri_state"))
      (node (ref "IC23") (pin "3") (pinfunction "Y4_3") (pintype "tri_state"))
      (node (ref "IC25") (pin "3") (pinfunction "Y4_3") (pintype "tri_state"))
    )
  )
)
